# StearnsN2b.net
KiCad netlist of a schematic drawn in EAGLE
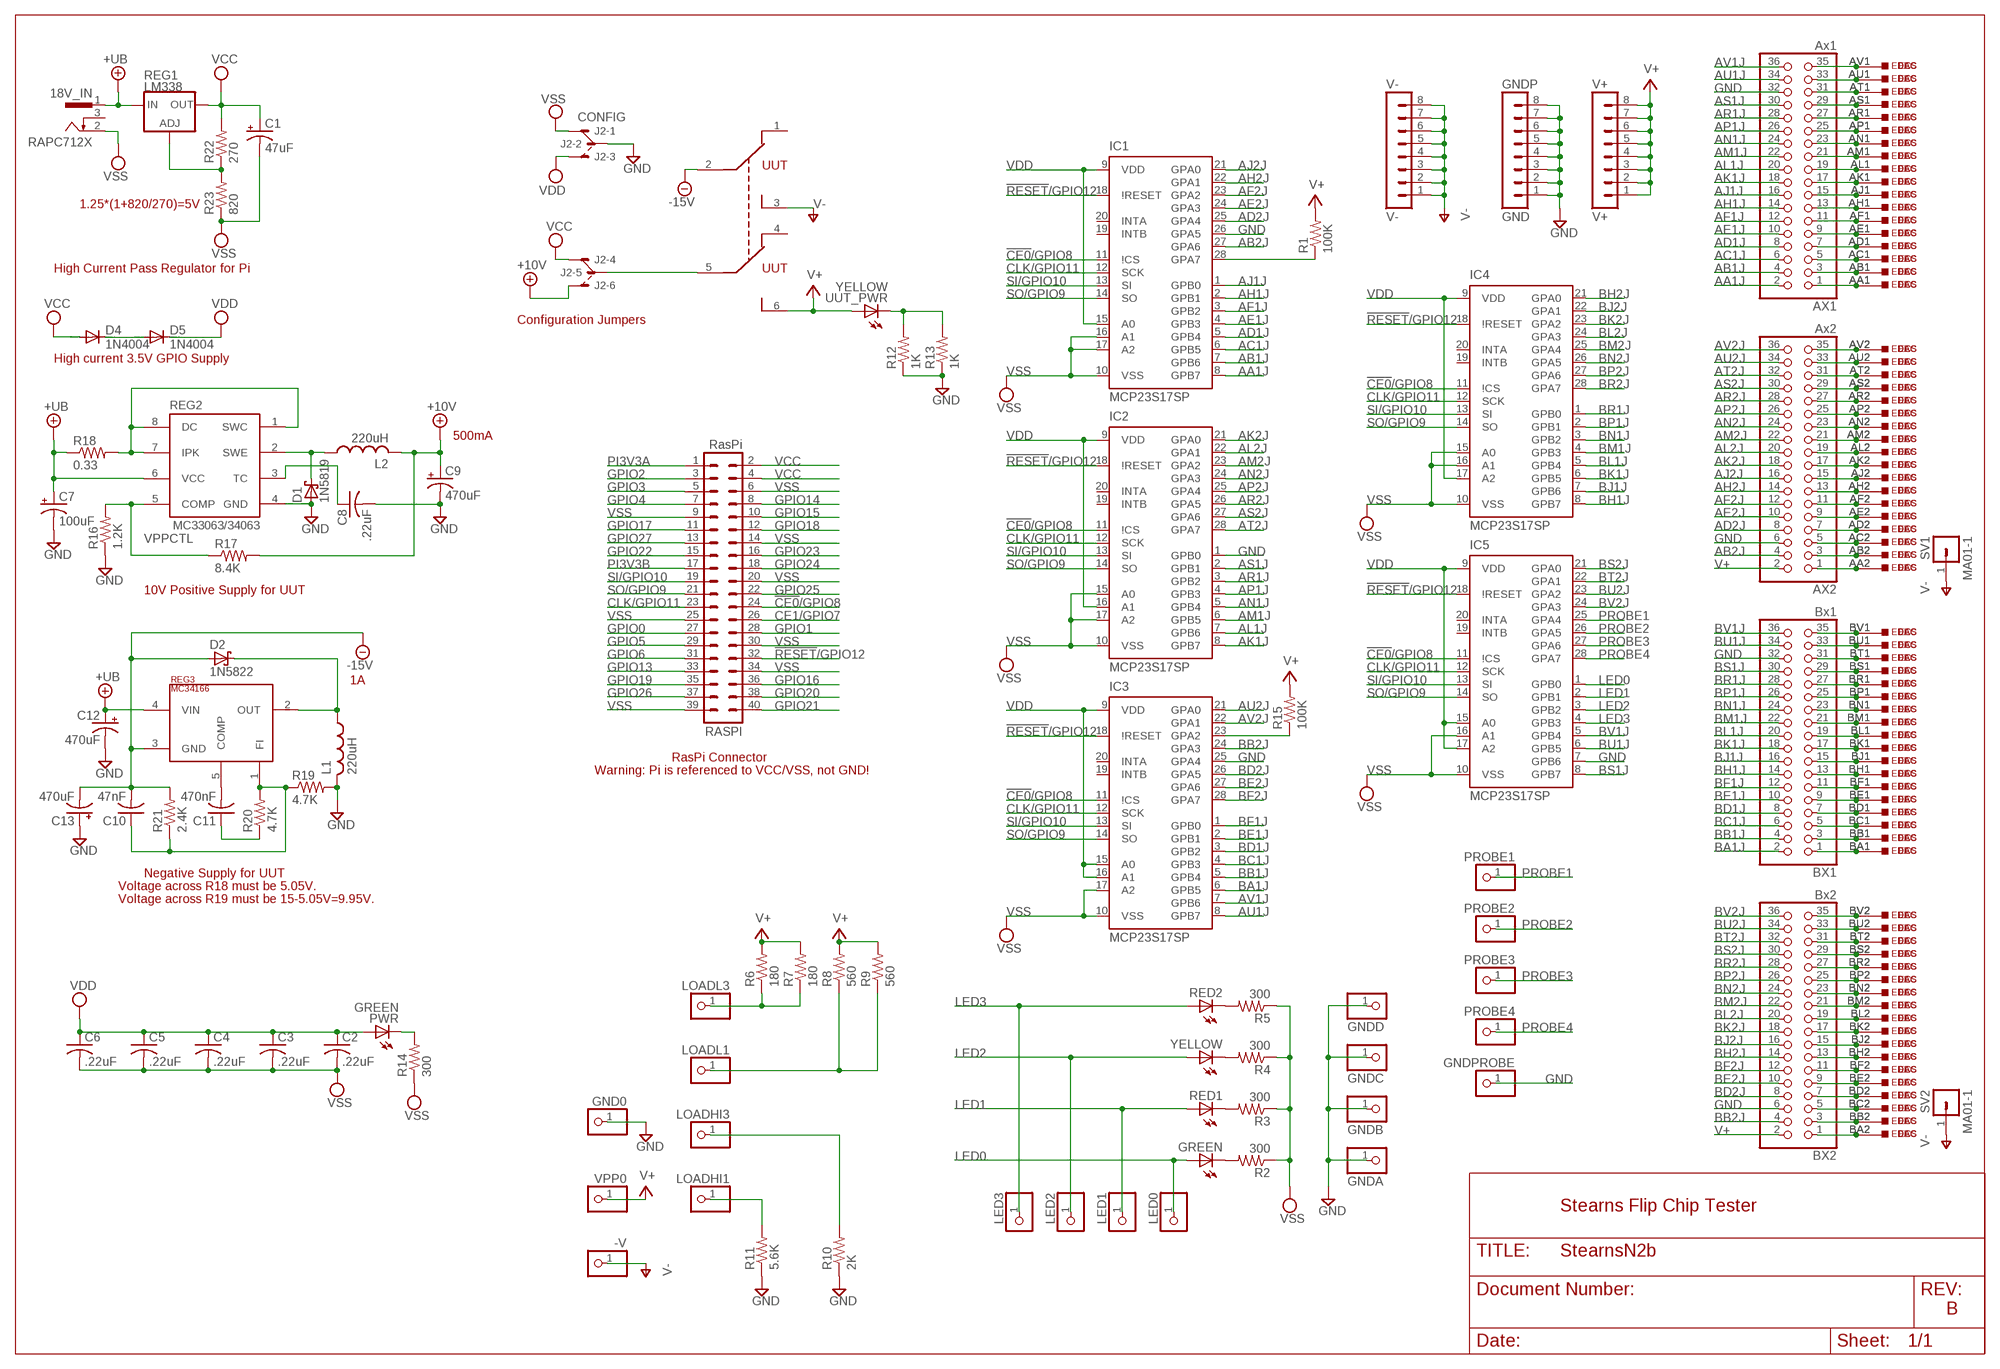
[diagram p0: schematic, sheet 1]

(export (version "E")
  (design (tool "Eeschema 10.0.6"))
  (components
    (comp (ref "-V")
      (value "PINHD-1X1")
      (footprint "eagle-import:1X01")
      (libsource (lib "eagle-import") (part "PINHD-1X1"))
    )
    (comp (ref "18V_IN")
      (value "RAPC712X")
      (footprint "eagle-import:SCD-014-A")
      (libsource (lib "eagle-import") (part "SCD-014A"))
    )
    (comp (ref "AX1")
      (value "Ax1")
      (footprint "eagle-import:2X18")
      (libsource (lib "eagle-import") (part "PINHD-2X18"))
    )
    (comp (ref "AX2")
      (value "Ax2")
      (footprint "eagle-import:2X18")
      (libsource (lib "eagle-import") (part "PINHD-2X18"))
    )
    (comp (ref "BX1")
      (value "Bx1")
      (footprint "eagle-import:2X18")
      (libsource (lib "eagle-import") (part "PINHD-2X18"))
    )
    (comp (ref "BX2")
      (value "Bx2")
      (footprint "eagle-import:2X18")
      (libsource (lib "eagle-import") (part "PINHD-2X18"))
    )
    (comp (ref "C1")
      (value "47uF")
      (footprint "eagle-import:E5-8,5")
      (libsource (lib "eagle-import") (part "CPOL-USE5-8.5"))
    )
    (comp (ref "C2")
      (value ".22uF")
      (footprint "eagle-import:C050-025X075")
      (libsource (lib "eagle-import") (part "C-US050-025X075"))
    )
    (comp (ref "C3")
      (value ".22uF")
      (footprint "eagle-import:C050-025X075")
      (libsource (lib "eagle-import") (part "C-US050-025X075"))
    )
    (comp (ref "C4")
      (value ".22uF")
      (footprint "eagle-import:C050-025X075")
      (libsource (lib "eagle-import") (part "C-US050-025X075"))
    )
    (comp (ref "C5")
      (value ".22uF")
      (footprint "eagle-import:C050-025X075")
      (libsource (lib "eagle-import") (part "C-US050-025X075"))
    )
    (comp (ref "C6")
      (value ".22uF")
      (footprint "eagle-import:C050-025X075")
      (libsource (lib "eagle-import") (part "C-US050-025X075"))
    )
    (comp (ref "C7")
      (value "100uF")
      (footprint "eagle-import:TT2D7")
      (libsource (lib "eagle-import") (part "CPOL-USTT2D7"))
    )
    (comp (ref "C8")
      (value ".22uF")
      (footprint "eagle-import:C050-025X075")
      (libsource (lib "eagle-import") (part "C-US050-025X075"))
    )
    (comp (ref "C9")
      (value "470uF")
      (footprint "eagle-import:E5-8,5")
      (libsource (lib "eagle-import") (part "CPOL-USE5-8.5"))
    )
    (comp (ref "C10")
      (value "47nF")
      (footprint "eagle-import:C050-025X075")
      (libsource (lib "eagle-import") (part "C-US050-025X075"))
    )
    (comp (ref "C11")
      (value "470nF")
      (footprint "eagle-import:C050-025X075")
      (libsource (lib "eagle-import") (part "C-US050-025X075"))
    )
    (comp (ref "C12")
      (value "470uF")
      (footprint "eagle-import:E5-8,5")
      (libsource (lib "eagle-import") (part "CPOL-USE5-8.5"))
    )
    (comp (ref "C13")
      (value "470uF")
      (footprint "eagle-import:E5-8,5")
      (libsource (lib "eagle-import") (part "CPOL-USE5-8.5"))
    )
    (comp (ref "D1")
      (value "1N5819")
      (footprint "eagle-import:DO35-7")
      (libsource (lib "eagle-import") (part "SCHOTTKY-DIODEDO35-7"))
    )
    (comp (ref "D2")
      (value "1N5822")
      (footprint "eagle-import:DO201T15")
      (libsource (lib "eagle-import") (part "SCHOTTKY-DIODEDO201T15"))
    )
    (comp (ref "D4")
      (value "1N4004")
      (footprint "eagle-import:DO41-10")
      (libsource (lib "eagle-import") (part "1N4004"))
    )
    (comp (ref "D5")
      (value "1N4004")
      (footprint "eagle-import:DO41-10")
      (libsource (lib "eagle-import") (part "1N4004"))
    )
    (comp (ref "DEC")
      (value "W971")
      (footprint "eagle-import:H807-2")
      (libsource (lib "eagle-import") (part "W971"))
    )
    (comp (ref "ECS")
      (value "W971ECS")
      (footprint "eagle-import:ECS2418-2")
      (libsource (lib "eagle-import") (part "W971ECS"))
    )
    (comp (ref "EDAC")
      (value "W971EDAC")
      (footprint "eagle-import:EDAC346-36-2")
      (libsource (lib "eagle-import") (part "W971EDAC"))
    )
    (comp (ref "GND0")
      (value "PINHD-1X1")
      (footprint "eagle-import:1X01")
      (libsource (lib "eagle-import") (part "PINHD-1X1"))
    )
    (comp (ref "GNDA")
      (value "PINHD-1X1")
      (footprint "eagle-import:1X01")
      (libsource (lib "eagle-import") (part "PINHD-1X1"))
    )
    (comp (ref "GNDB")
      (value "PINHD-1X1")
      (footprint "eagle-import:1X01")
      (libsource (lib "eagle-import") (part "PINHD-1X1"))
    )
    (comp (ref "GNDC")
      (value "PINHD-1X1")
      (footprint "eagle-import:1X01")
      (libsource (lib "eagle-import") (part "PINHD-1X1"))
    )
    (comp (ref "GNDD")
      (value "PINHD-1X1")
      (footprint "eagle-import:1X01")
      (libsource (lib "eagle-import") (part "PINHD-1X1"))
    )
    (comp (ref "GNDP")
      (value "GND")
      (footprint "eagle-import:MA08-1")
      (libsource (lib "eagle-import") (part "MA08-1"))
    )
    (comp (ref "GNDPROBE")
      (value "PINHD-1X1")
      (footprint "eagle-import:1X01")
      (libsource (lib "eagle-import") (part "PINHD-1X1"))
    )
    (comp (ref "GREEN")
      (value "LED5MM")
      (footprint "eagle-import:LED5MM")
      (libsource (lib "eagle-import") (part "LED5MM"))
    )
    (comp (ref "IC1")
      (value "MCP23S17SP")
      (footprint "eagle-import:DIL28-3")
      (libsource (lib "eagle-import") (part "MCP23S17SP"))
    )
    (comp (ref "IC2")
      (value "MCP23S17SP")
      (footprint "eagle-import:DIL28-3")
      (libsource (lib "eagle-import") (part "MCP23S17SP"))
    )
    (comp (ref "IC3")
      (value "MCP23S17SP")
      (footprint "eagle-import:DIL28-3")
      (libsource (lib "eagle-import") (part "MCP23S17SP"))
    )
    (comp (ref "IC4")
      (value "MCP23S17SP")
      (footprint "eagle-import:DIL28-3")
      (libsource (lib "eagle-import") (part "MCP23S17SP"))
    )
    (comp (ref "IC5")
      (value "MCP23S17SP")
      (footprint "eagle-import:DIL28-3")
      (libsource (lib "eagle-import") (part "MCP23S17SP"))
    )
    (comp (ref "J2")
      (value "CONFIG")
      (footprint "eagle-import:22-23-2061")
      (fields (field (name "MF") "MOLEX") (field (name "MPN") "22-23-2061"))
      (libsource (lib "eagle-import") (part "22-23-2061"))
    )
    (comp (ref "L1")
      (value "220uH")
      (footprint "eagle-import:6000-XXXX-RC")
      (libsource (lib "eagle-import") (part "L-US6000-XXX-RC"))
    )
    (comp (ref "L2")
      (value "220uH")
      (footprint "eagle-import:6000-XXXX-RC")
      (libsource (lib "eagle-import") (part "L-US6000-XXX-RC"))
    )
    (comp (ref "LED0")
      (value "PINHD-1X1")
      (footprint "eagle-import:1X01")
      (libsource (lib "eagle-import") (part "PINHD-1X1"))
    )
    (comp (ref "LED1")
      (value "PINHD-1X1")
      (footprint "eagle-import:1X01")
      (libsource (lib "eagle-import") (part "PINHD-1X1"))
    )
    (comp (ref "LED2")
      (value "PINHD-1X1")
      (footprint "eagle-import:1X01")
      (libsource (lib "eagle-import") (part "PINHD-1X1"))
    )
    (comp (ref "LED3")
      (value "PINHD-1X1")
      (footprint "eagle-import:1X01")
      (libsource (lib "eagle-import") (part "PINHD-1X1"))
    )
    (comp (ref "LOADHI1")
      (value "PINHD-1X1")
      (footprint "eagle-import:1X01")
      (libsource (lib "eagle-import") (part "PINHD-1X1"))
    )
    (comp (ref "LOADHI3")
      (value "PINHD-1X1")
      (footprint "eagle-import:1X01")
      (libsource (lib "eagle-import") (part "PINHD-1X1"))
    )
    (comp (ref "LOADL1")
      (value "PINHD-1X1")
      (footprint "eagle-import:1X01")
      (libsource (lib "eagle-import") (part "PINHD-1X1"))
    )
    (comp (ref "LOADL3")
      (value "PINHD-1X1")
      (footprint "eagle-import:1X01")
      (libsource (lib "eagle-import") (part "PINHD-1X1"))
    )
    (comp (ref "PROBE1")
      (value "PINHD-1X1")
      (footprint "eagle-import:1X01")
      (libsource (lib "eagle-import") (part "PINHD-1X1"))
    )
    (comp (ref "PROBE2")
      (value "PINHD-1X1")
      (footprint "eagle-import:1X01")
      (libsource (lib "eagle-import") (part "PINHD-1X1"))
    )
    (comp (ref "PROBE3")
      (value "PINHD-1X1")
      (footprint "eagle-import:1X01")
      (libsource (lib "eagle-import") (part "PINHD-1X1"))
    )
    (comp (ref "PROBE4")
      (value "PINHD-1X1")
      (footprint "eagle-import:1X01")
      (libsource (lib "eagle-import") (part "PINHD-1X1"))
    )
    (comp (ref "PWR")
      (value "GREEN")
      (footprint "eagle-import:LED5MM")
      (libsource (lib "eagle-import") (part "LED5MM"))
    )
    (comp (ref "R1")
      (value "100K")
      (footprint "eagle-import:0207_10")
      (libsource (lib "eagle-import") (part "R-US_0207/10"))
    )
    (comp (ref "R2")
      (value "300")
      (footprint "eagle-import:0207_10")
      (libsource (lib "eagle-import") (part "R-US_0207/10"))
    )
    (comp (ref "R3")
      (value "300")
      (footprint "eagle-import:0207_10")
      (libsource (lib "eagle-import") (part "R-US_0207/10"))
    )
    (comp (ref "R4")
      (value "300")
      (footprint "eagle-import:0207_10")
      (libsource (lib "eagle-import") (part "R-US_0207/10"))
    )
    (comp (ref "R5")
      (value "300")
      (footprint "eagle-import:0207_10")
      (libsource (lib "eagle-import") (part "R-US_0207/10"))
    )
    (comp (ref "R6")
      (value "180")
      (footprint "eagle-import:0207_10")
      (libsource (lib "eagle-import") (part "R-US_0207/10"))
    )
    (comp (ref "R7")
      (value "180")
      (footprint "eagle-import:0207_10")
      (libsource (lib "eagle-import") (part "R-US_0207/10"))
    )
    (comp (ref "R8")
      (value "560")
      (footprint "eagle-import:0207_10")
      (libsource (lib "eagle-import") (part "R-US_0207/10"))
    )
    (comp (ref "R9")
      (value "560")
      (footprint "eagle-import:0207_10")
      (libsource (lib "eagle-import") (part "R-US_0207/10"))
    )
    (comp (ref "R10")
      (value "2K")
      (footprint "eagle-import:0207_10")
      (libsource (lib "eagle-import") (part "R-US_0207/10"))
    )
    (comp (ref "R11")
      (value "5.6K")
      (footprint "eagle-import:0207_10")
      (libsource (lib "eagle-import") (part "R-US_0207/10"))
    )
    (comp (ref "R12")
      (value "1K")
      (footprint "eagle-import:0207_10")
      (libsource (lib "eagle-import") (part "R-US_0207/10"))
    )
    (comp (ref "R13")
      (value "1K")
      (footprint "eagle-import:0207_10")
      (libsource (lib "eagle-import") (part "R-US_0207/10"))
    )
    (comp (ref "R14")
      (value "300")
      (footprint "eagle-import:0207_10")
      (libsource (lib "eagle-import") (part "R-US_0207/10"))
    )
    (comp (ref "R15")
      (value "100K")
      (footprint "eagle-import:0207_10")
      (libsource (lib "eagle-import") (part "R-US_0207/10"))
    )
    (comp (ref "R16")
      (value "1.2K")
      (footprint "eagle-import:0207_10")
      (libsource (lib "eagle-import") (part "R-US_0207/10"))
    )
    (comp (ref "R17")
      (value "8.4K")
      (footprint "eagle-import:0207_10")
      (libsource (lib "eagle-import") (part "R-US_0207/10"))
    )
    (comp (ref "R18")
      (value "0.33")
      (footprint "eagle-import:0207_10")
      (libsource (lib "eagle-import") (part "R-US_0207/10"))
    )
    (comp (ref "R19")
      (value "4.7K")
      (footprint "eagle-import:0207_10")
      (libsource (lib "eagle-import") (part "R-US_0207/10"))
    )
    (comp (ref "R20")
      (value "4.7K")
      (footprint "eagle-import:0207_10")
      (libsource (lib "eagle-import") (part "R-US_0207/10"))
    )
    (comp (ref "R21")
      (value "2.4K")
      (footprint "eagle-import:0207_10")
      (libsource (lib "eagle-import") (part "R-US_0207/10"))
    )
    (comp (ref "R22")
      (value "270")
      (footprint "eagle-import:0207_10")
      (libsource (lib "eagle-import") (part "R-US_0207/10"))
    )
    (comp (ref "R23")
      (value "820")
      (footprint "eagle-import:0207_10")
      (libsource (lib "eagle-import") (part "R-US_0207/10"))
    )
    (comp (ref "RASPI")
      (value "RasPi")
      (footprint "eagle-import:MA20-2")
      (libsource (lib "eagle-import") (part "MA20-2"))
    )
    (comp (ref "RED1")
      (value "LED5MM")
      (footprint "eagle-import:LED5MM")
      (libsource (lib "eagle-import") (part "LED5MM"))
    )
    (comp (ref "RED2")
      (value "LED5MM")
      (footprint "eagle-import:LED5MM")
      (libsource (lib "eagle-import") (part "LED5MM"))
    )
    (comp (ref "REG1")
      (value "LM338")
      (footprint "eagle-import:TO220L1")
      (libsource (lib "eagle-import") (part "LM138-TL"))
    )
    (comp (ref "REG2")
      (value "MC33063/MC34063P")
      (footprint "eagle-import:DIL08")
      (libsource (lib "eagle-import") (part "MC33063/MC34063P"))
    )
    (comp (ref "REG3")
      (value "MC34166")
      (footprint "eagle-import:TO220-52")
      (libsource (lib "eagle-import") (part "MC34166"))
    )
    (comp (ref "SV1")
      (value "MA01-1")
      (footprint "eagle-import:MA01-1")
      (libsource (lib "eagle-import") (part "MA01-1"))
    )
    (comp (ref "SV2")
      (value "MA01-1")
      (footprint "eagle-import:MA01-1")
      (libsource (lib "eagle-import") (part "MA01-1"))
    )
    (comp (ref "UUT")
      (value "720X")
      (footprint "eagle-import:7209MD9V3")
      (libsource (lib "eagle-import") (part "720X"))
    )
    (comp (ref "UUT_PWR")
      (value "YELLOW")
      (footprint "eagle-import:LED5MM")
      (libsource (lib "eagle-import") (part "LED5MM"))
    )
    (comp (ref "V+")
      (value "V+")
      (footprint "eagle-import:MA08-1")
      (libsource (lib "eagle-import") (part "MA08-1"))
    )
    (comp (ref "V-")
      (value "V-")
      (footprint "eagle-import:MA08-1")
      (libsource (lib "eagle-import") (part "MA08-1"))
    )
    (comp (ref "VPP0")
      (value "PINHD-1X1")
      (footprint "eagle-import:1X01")
      (libsource (lib "eagle-import") (part "PINHD-1X1"))
    )
    (comp (ref "YELLOW")
      (value "LED5MM")
      (footprint "eagle-import:LED5MM")
      (libsource (lib "eagle-import") (part "LED5MM"))
    )
  )
  (nets
    (net (code "1") (name "+10V") (class "Default")
      (node (ref "C9") (pin "+") (pinfunction "+_+") (pintype "passive"))
      (node (ref "J2") (pin "6") (pinfunction "S_6") (pintype "passive"))
      (node (ref "L2") (pin "2") (pinfunction "2_2") (pintype "passive"))
      (node (ref "R17") (pin "2") (pinfunction "2_2") (pintype "passive"))
    )
    (net (code "2") (name "+UB") (class "Default")
      (node (ref "18V_IN") (pin "1") (pinfunction "1_1") (pintype "passive"))
      (node (ref "C12") (pin "+") (pinfunction "+_+") (pintype "passive"))
      (node (ref "C7") (pin "+") (pinfunction "+_+") (pintype "passive"))
      (node (ref "R18") (pin "1") (pinfunction "1_1") (pintype "passive"))
      (node (ref "REG1") (pin "3") (pinfunction "IN_3") (pintype "input"))
      (node (ref "REG2") (pin "6") (pinfunction "VCC_6") (pintype "power_in"))
      (node (ref "REG3") (pin "4") (pinfunction "VIN_4") (pintype "input"))
    )
    (net (code "3") (name "-15V") (class "Default")
      (node (ref "C10") (pin "2") (pinfunction "2_2") (pintype "passive"))
      (node (ref "C13") (pin "-") (pinfunction "-_-") (pintype "passive"))
      (node (ref "D2") (pin "A") (pinfunction "A_A") (pintype "passive"))
      (node (ref "R21") (pin "2") (pinfunction "2_2") (pintype "passive"))
      (node (ref "REG3") (pin "3") (pinfunction "GND_3") (pintype "input"))
      (node (ref "UUT") (pin "2") (pinfunction "A2_2") (pintype "bidirectional"))
    )
    (net (code "4") (name "/AA1J") (class "Default")
      (node (ref "AX1") (pin "2") (pinfunction "2_2") (pintype "passive"))
      (node (ref "IC1") (pin "8") (pinfunction "GPB7_8") (pintype "bidirectional"))
    )
    (net (code "5") (name "/AB1J") (class "Default")
      (node (ref "AX1") (pin "4") (pinfunction "4_4") (pintype "passive"))
      (node (ref "IC1") (pin "7") (pinfunction "GPB6_7") (pintype "bidirectional"))
    )
    (net (code "6") (name "/AB2J") (class "Default")
      (node (ref "AX2") (pin "4") (pinfunction "4_4") (pintype "passive"))
      (node (ref "IC1") (pin "27") (pinfunction "GPA6_27") (pintype "bidirectional"))
    )
    (net (code "7") (name "/AC1J") (class "Default")
      (node (ref "AX1") (pin "6") (pinfunction "6_6") (pintype "passive"))
      (node (ref "IC1") (pin "6") (pinfunction "GPB5_6") (pintype "bidirectional"))
    )
    (net (code "8") (name "/AD1J") (class "Default")
      (node (ref "AX1") (pin "8") (pinfunction "8_8") (pintype "passive"))
      (node (ref "IC1") (pin "5") (pinfunction "GPB4_5") (pintype "bidirectional"))
    )
    (net (code "9") (name "/AD2J") (class "Default")
      (node (ref "AX2") (pin "8") (pinfunction "8_8") (pintype "passive"))
      (node (ref "IC1") (pin "25") (pinfunction "GPA4_25") (pintype "bidirectional"))
    )
    (net (code "10") (name "/AE1J") (class "Default")
      (node (ref "AX1") (pin "10") (pinfunction "10_10") (pintype "passive"))
      (node (ref "IC1") (pin "4") (pinfunction "GPB3_4") (pintype "bidirectional"))
    )
    (net (code "11") (name "/AE2J") (class "Default")
      (node (ref "AX2") (pin "10") (pinfunction "10_10") (pintype "passive"))
      (node (ref "IC1") (pin "24") (pinfunction "GPA3_24") (pintype "bidirectional"))
    )
    (net (code "12") (name "/AF1J") (class "Default")
      (node (ref "AX1") (pin "12") (pinfunction "12_12") (pintype "passive"))
      (node (ref "IC1") (pin "3") (pinfunction "GPB2_3") (pintype "bidirectional"))
    )
    (net (code "13") (name "/AF2J") (class "Default")
      (node (ref "AX2") (pin "12") (pinfunction "12_12") (pintype "passive"))
      (node (ref "IC1") (pin "23") (pinfunction "GPA2_23") (pintype "bidirectional"))
    )
    (net (code "14") (name "/AH1J") (class "Default")
      (node (ref "AX1") (pin "14") (pinfunction "14_14") (pintype "passive"))
      (node (ref "IC1") (pin "2") (pinfunction "GPB1_2") (pintype "bidirectional"))
    )
    (net (code "15") (name "/AH2J") (class "Default")
      (node (ref "AX2") (pin "14") (pinfunction "14_14") (pintype "passive"))
      (node (ref "IC1") (pin "22") (pinfunction "GPA1_22") (pintype "bidirectional"))
    )
    (net (code "16") (name "/AJ1J") (class "Default")
      (node (ref "AX1") (pin "16") (pinfunction "16_16") (pintype "passive"))
      (node (ref "IC1") (pin "1") (pinfunction "GPB0_1") (pintype "bidirectional"))
    )
    (net (code "17") (name "/AJ2J") (class "Default")
      (node (ref "AX2") (pin "16") (pinfunction "16_16") (pintype "passive"))
      (node (ref "IC1") (pin "21") (pinfunction "GPA0_21") (pintype "bidirectional"))
    )
    (net (code "18") (name "/AK1J") (class "Default")
      (node (ref "AX1") (pin "18") (pinfunction "18_18") (pintype "passive"))
      (node (ref "IC2") (pin "8") (pinfunction "GPB7_8") (pintype "bidirectional"))
    )
    (net (code "19") (name "/AK2J") (class "Default")
      (node (ref "AX2") (pin "18") (pinfunction "18_18") (pintype "passive"))
      (node (ref "IC2") (pin "21") (pinfunction "GPA0_21") (pintype "bidirectional"))
    )
    (net (code "20") (name "/AL1J") (class "Default")
      (node (ref "AX1") (pin "20") (pinfunction "20_20") (pintype "passive"))
      (node (ref "IC2") (pin "7") (pinfunction "GPB6_7") (pintype "bidirectional"))
    )
    (net (code "21") (name "/AL2J") (class "Default")
      (node (ref "AX2") (pin "20") (pinfunction "20_20") (pintype "passive"))
      (node (ref "IC2") (pin "22") (pinfunction "GPA1_22") (pintype "bidirectional"))
    )
    (net (code "22") (name "/AM1J") (class "Default")
      (node (ref "AX1") (pin "22") (pinfunction "22_22") (pintype "passive"))
      (node (ref "IC2") (pin "6") (pinfunction "GPB5_6") (pintype "bidirectional"))
    )
    (net (code "23") (name "/AM2J") (class "Default")
      (node (ref "AX2") (pin "22") (pinfunction "22_22") (pintype "passive"))
      (node (ref "IC2") (pin "23") (pinfunction "GPA2_23") (pintype "bidirectional"))
    )
    (net (code "24") (name "/AN1J") (class "Default")
      (node (ref "AX1") (pin "24") (pinfunction "24_24") (pintype "passive"))
      (node (ref "IC2") (pin "5") (pinfunction "GPB4_5") (pintype "bidirectional"))
    )
    (net (code "25") (name "/AN2J") (class "Default")
      (node (ref "AX2") (pin "24") (pinfunction "24_24") (pintype "passive"))
      (node (ref "IC2") (pin "24") (pinfunction "GPA3_24") (pintype "bidirectional"))
    )
    (net (code "26") (name "/AP1J") (class "Default")
      (node (ref "AX1") (pin "26") (pinfunction "26_26") (pintype "passive"))
      (node (ref "IC2") (pin "4") (pinfunction "GPB3_4") (pintype "bidirectional"))
    )
    (net (code "27") (name "/AP2J") (class "Default")
      (node (ref "AX2") (pin "26") (pinfunction "26_26") (pintype "passive"))
      (node (ref "IC2") (pin "25") (pinfunction "GPA4_25") (pintype "bidirectional"))
    )
    (net (code "28") (name "/AR1J") (class "Default")
      (node (ref "AX1") (pin "28") (pinfunction "28_28") (pintype "passive"))
      (node (ref "IC2") (pin "3") (pinfunction "GPB2_3") (pintype "bidirectional"))
    )
    (net (code "29") (name "/AR2J") (class "Default")
      (node (ref "AX2") (pin "28") (pinfunction "28_28") (pintype "passive"))
      (node (ref "IC2") (pin "26") (pinfunction "GPA5_26") (pintype "bidirectional"))
    )
    (net (code "30") (name "/AS1J") (class "Default")
      (node (ref "AX1") (pin "30") (pinfunction "30_30") (pintype "passive"))
      (node (ref "IC2") (pin "2") (pinfunction "GPB1_2") (pintype "bidirectional"))
    )
    (net (code "31") (name "/AS2J") (class "Default")
      (node (ref "AX2") (pin "30") (pinfunction "30_30") (pintype "passive"))
      (node (ref "IC2") (pin "27") (pinfunction "GPA6_27") (pintype "bidirectional"))
    )
    (net (code "32") (name "/AT2J") (class "Default")
      (node (ref "AX2") (pin "32") (pinfunction "32_32") (pintype "passive"))
      (node (ref "IC2") (pin "28") (pinfunction "GPA7_28") (pintype "bidirectional"))
    )
    (net (code "33") (name "/AU1J") (class "Default")
      (node (ref "AX1") (pin "34") (pinfunction "34_34") (pintype "passive"))
      (node (ref "IC3") (pin "8") (pinfunction "GPB7_8") (pintype "bidirectional"))
    )
    (net (code "34") (name "/AU2J") (class "Default")
      (node (ref "AX2") (pin "34") (pinfunction "34_34") (pintype "passive"))
      (node (ref "IC3") (pin "21") (pinfunction "GPA0_21") (pintype "bidirectional"))
    )
    (net (code "35") (name "/AV1J") (class "Default")
      (node (ref "AX1") (pin "36") (pinfunction "36_36") (pintype "passive"))
      (node (ref "IC3") (pin "7") (pinfunction "GPB6_7") (pintype "bidirectional"))
    )
    (net (code "36") (name "/AV2J") (class "Default")
      (node (ref "AX2") (pin "36") (pinfunction "36_36") (pintype "passive"))
      (node (ref "IC3") (pin "22") (pinfunction "GPA1_22") (pintype "bidirectional"))
    )
    (net (code "37") (name "/BA1J") (class "Default")
      (node (ref "BX1") (pin "2") (pinfunction "2_2") (pintype "passive"))
      (node (ref "IC3") (pin "6") (pinfunction "GPB5_6") (pintype "bidirectional"))
    )
    (net (code "38") (name "/BB1J") (class "Default")
      (node (ref "BX1") (pin "4") (pinfunction "4_4") (pintype "passive"))
      (node (ref "IC3") (pin "5") (pinfunction "GPB4_5") (pintype "bidirectional"))
    )
    (net (code "39") (name "/BB2J") (class "Default")
      (node (ref "BX2") (pin "4") (pinfunction "4_4") (pintype "passive"))
      (node (ref "IC3") (pin "24") (pinfunction "GPA3_24") (pintype "bidirectional"))
    )
    (net (code "40") (name "/BC1J") (class "Default")
      (node (ref "BX1") (pin "6") (pinfunction "6_6") (pintype "passive"))
      (node (ref "IC3") (pin "4") (pinfunction "GPB3_4") (pintype "bidirectional"))
    )
    (net (code "41") (name "/BD1J") (class "Default")
      (node (ref "BX1") (pin "8") (pinfunction "8_8") (pintype "passive"))
      (node (ref "IC3") (pin "3") (pinfunction "GPB2_3") (pintype "bidirectional"))
    )
    (net (code "42") (name "/BD2J") (class "Default")
      (node (ref "BX2") (pin "8") (pinfunction "8_8") (pintype "passive"))
      (node (ref "IC3") (pin "26") (pinfunction "GPA5_26") (pintype "bidirectional"))
    )
    (net (code "43") (name "/BE1J") (class "Default")
      (node (ref "BX1") (pin "10") (pinfunction "10_10") (pintype "passive"))
      (node (ref "IC3") (pin "2") (pinfunction "GPB1_2") (pintype "bidirectional"))
    )
    (net (code "44") (name "/BE2J") (class "Default")
      (node (ref "BX2") (pin "10") (pinfunction "10_10") (pintype "passive"))
      (node (ref "IC3") (pin "27") (pinfunction "GPA6_27") (pintype "bidirectional"))
    )
    (net (code "45") (name "/BF1J") (class "Default")
      (node (ref "BX1") (pin "12") (pinfunction "12_12") (pintype "passive"))
      (node (ref "IC3") (pin "1") (pinfunction "GPB0_1") (pintype "bidirectional"))
    )
    (net (code "46") (name "/BF2J") (class "Default")
      (node (ref "BX2") (pin "12") (pinfunction "12_12") (pintype "passive"))
      (node (ref "IC3") (pin "28") (pinfunction "GPA7_28") (pintype "bidirectional"))
    )
    (net (code "47") (name "/BH1J") (class "Default")
      (node (ref "BX1") (pin "14") (pinfunction "14_14") (pintype "passive"))
      (node (ref "IC4") (pin "8") (pinfunction "GPB7_8") (pintype "bidirectional"))
    )
    (net (code "48") (name "/BH2J") (class "Default")
      (node (ref "BX2") (pin "14") (pinfunction "14_14") (pintype "passive"))
      (node (ref "IC4") (pin "21") (pinfunction "GPA0_21") (pintype "bidirectional"))
    )
    (net (code "49") (name "/BJ1J") (class "Default")
      (node (ref "BX1") (pin "16") (pinfunction "16_16") (pintype "passive"))
      (node (ref "IC4") (pin "7") (pinfunction "GPB6_7") (pintype "bidirectional"))
    )
    (net (code "50") (name "/BJ2J") (class "Default")
      (node (ref "BX2") (pin "16") (pinfunction "16_16") (pintype "passive"))
      (node (ref "IC4") (pin "22") (pinfunction "GPA1_22") (pintype "bidirectional"))
    )
    (net (code "51") (name "/BK1J") (class "Default")
      (node (ref "BX1") (pin "18") (pinfunction "18_18") (pintype "passive"))
      (node (ref "IC4") (pin "6") (pinfunction "GPB5_6") (pintype "bidirectional"))
    )
    (net (code "52") (name "/BK2J") (class "Default")
      (node (ref "BX2") (pin "18") (pinfunction "18_18") (pintype "passive"))
      (node (ref "IC4") (pin "23") (pinfunction "GPA2_23") (pintype "bidirectional"))
    )
    (net (code "53") (name "/BL1J") (class "Default")
      (node (ref "BX1") (pin "20") (pinfunction "20_20") (pintype "passive"))
      (node (ref "IC4") (pin "5") (pinfunction "GPB4_5") (pintype "bidirectional"))
    )
    (net (code "54") (name "/BL2J") (class "Default")
      (node (ref "BX2") (pin "20") (pinfunction "20_20") (pintype "passive"))
      (node (ref "IC4") (pin "24") (pinfunction "GPA3_24") (pintype "bidirectional"))
    )
    (net (code "55") (name "/BM1J") (class "Default")
      (node (ref "BX1") (pin "22") (pinfunction "22_22") (pintype "passive"))
      (node (ref "IC4") (pin "4") (pinfunction "GPB3_4") (pintype "bidirectional"))
    )
    (net (code "56") (name "/BM2J") (class "Default")
      (node (ref "BX2") (pin "22") (pinfunction "22_22") (pintype "passive"))
      (node (ref "IC4") (pin "25") (pinfunction "GPA4_25") (pintype "bidirectional"))
    )
    (net (code "57") (name "/BN1J") (class "Default")
      (node (ref "BX1") (pin "24") (pinfunction "24_24") (pintype "passive"))
      (node (ref "IC4") (pin "3") (pinfunction "GPB2_3") (pintype "bidirectional"))
    )
    (net (code "58") (name "/BN2J") (class "Default")
      (node (ref "BX2") (pin "24") (pinfunction "24_24") (pintype "passive"))
      (node (ref "IC4") (pin "26") (pinfunction "GPA5_26") (pintype "bidirectional"))
    )
    (net (code "59") (name "/BP1J") (class "Default")
      (node (ref "BX1") (pin "26") (pinfunction "26_26") (pintype "passive"))
      (node (ref "IC4") (pin "2") (pinfunction "GPB1_2") (pintype "bidirectional"))
    )
    (net (code "60") (name "/BP2J") (class "Default")
      (node (ref "BX2") (pin "26") (pinfunction "26_26") (pintype "passive"))
      (node (ref "IC4") (pin "27") (pinfunction "GPA6_27") (pintype "bidirectional"))
    )
    (net (code "61") (name "/BR1J") (class "Default")
      (node (ref "BX1") (pin "28") (pinfunction "28_28") (pintype "passive"))
      (node (ref "IC4") (pin "1") (pinfunction "GPB0_1") (pintype "bidirectional"))
    )
    (net (code "62") (name "/BR2J") (class "Default")
      (node (ref "BX2") (pin "28") (pinfunction "28_28") (pintype "passive"))
      (node (ref "IC4") (pin "28") (pinfunction "GPA7_28") (pintype "bidirectional"))
    )
    (net (code "63") (name "/BS1J") (class "Default")
      (node (ref "BX1") (pin "30") (pinfunction "30_30") (pintype "passive"))
      (node (ref "IC5") (pin "8") (pinfunction "GPB7_8") (pintype "bidirectional"))
    )
    (net (code "64") (name "/BS2J") (class "Default")
      (node (ref "BX2") (pin "30") (pinfunction "30_30") (pintype "passive"))
      (node (ref "IC5") (pin "21") (pinfunction "GPA0_21") (pintype "bidirectional"))
    )
    (net (code "65") (name "/BT2J") (class "Default")
      (node (ref "BX2") (pin "32") (pinfunction "32_32") (pintype "passive"))
      (node (ref "IC5") (pin "22") (pinfunction "GPA1_22") (pintype "bidirectional"))
    )
    (net (code "66") (name "/BU1J") (class "Default")
      (node (ref "BX1") (pin "34") (pinfunction "34_34") (pintype "passive"))
      (node (ref "IC5") (pin "6") (pinfunction "GPB5_6") (pintype "bidirectional"))
    )
    (net (code "67") (name "/BU2J") (class "Default")
      (node (ref "BX2") (pin "34") (pinfunction "34_34") (pintype "passive"))
      (node (ref "IC5") (pin "23") (pinfunction "GPA2_23") (pintype "bidirectional"))
    )
    (net (code "68") (name "/BV1J") (class "Default")
      (node (ref "BX1") (pin "36") (pinfunction "36_36") (pintype "passive"))
      (node (ref "IC5") (pin "5") (pinfunction "GPB4_5") (pintype "bidirectional"))
    )
    (net (code "69") (name "/BV2J") (class "Default")
      (node (ref "BX2") (pin "36") (pinfunction "36_36") (pintype "passive"))
      (node (ref "IC5") (pin "24") (pinfunction "GPA3_24") (pintype "bidirectional"))
    )
    (net (code "70") (name "/CE1{slash}GPIO7") (class "Default")
      (node (ref "RASPI") (pin "26") (pinfunction "26_26") (pintype "passive"))
    )
    (net (code "71") (name "/CLK{slash}GPIO11") (class "Default")
      (node (ref "IC1") (pin "12") (pinfunction "SCK_12") (pintype "input"))
      (node (ref "IC2") (pin "12") (pinfunction "SCK_12") (pintype "input"))
      (node (ref "IC3") (pin "12") (pinfunction "SCK_12") (pintype "input"))
      (node (ref "IC4") (pin "12") (pinfunction "SCK_12") (pintype "input"))
      (node (ref "IC5") (pin "12") (pinfunction "SCK_12") (pintype "input"))
      (node (ref "RASPI") (pin "23") (pinfunction "23_23") (pintype "passive"))
    )
    (net (code "72") (name "/GPIO0") (class "Default")
      (node (ref "RASPI") (pin "27") (pinfunction "27_27") (pintype "passive"))
    )
    (net (code "73") (name "/GPIO1") (class "Default")
      (node (ref "RASPI") (pin "28") (pinfunction "28_28") (pintype "passive"))
    )
    (net (code "74") (name "/GPIO2") (class "Default")
      (node (ref "RASPI") (pin "3") (pinfunction "3_3") (pintype "passive"))
    )
    (net (code "75") (name "/GPIO3") (class "Default")
      (node (ref "RASPI") (pin "5") (pinfunction "5_5") (pintype "passive"))
    )
    (net (code "76") (name "/GPIO4") (class "Default")
      (node (ref "RASPI") (pin "7") (pinfunction "7_7") (pintype "passive"))
    )
    (net (code "77") (name "/GPIO5") (class "Default")
      (node (ref "RASPI") (pin "29") (pinfunction "29_29") (pintype "passive"))
    )
    (net (code "78") (name "/GPIO6") (class "Default")
      (node (ref "RASPI") (pin "31") (pinfunction "31_31") (pintype "passive"))
    )
    (net (code "79") (name "/GPIO13") (class "Default")
      (node (ref "RASPI") (pin "33") (pinfunction "33_33") (pintype "passive"))
    )
    (net (code "80") (name "/GPIO14") (class "Default")
      (node (ref "RASPI") (pin "8") (pinfunction "8_8") (pintype "passive"))
    )
    (net (code "81") (name "/GPIO15") (class "Default")
      (node (ref "RASPI") (pin "10") (pinfunction "10_10") (pintype "passive"))
    )
    (net (code "82") (name "/GPIO16") (class "Default")
      (node (ref "RASPI") (pin "36") (pinfunction "36_36") (pintype "passive"))
    )
    (net (code "83") (name "/GPIO17") (class "Default")
      (node (ref "RASPI") (pin "11") (pinfunction "11_11") (pintype "passive"))
    )
    (net (code "84") (name "/GPIO18") (class "Default")
      (node (ref "RASPI") (pin "12") (pinfunction "12_12") (pintype "passive"))
    )
    (net (code "85") (name "/GPIO19") (class "Default")
      (node (ref "RASPI") (pin "35") (pinfunction "35_35") (pintype "passive"))
    )
    (net (code "86") (name "/GPIO20") (class "Default")
      (node (ref "RASPI") (pin "38") (pinfunction "38_38") (pintype "passive"))
    )
    (net (code "87") (name "/GPIO21") (class "Default")
      (node (ref "RASPI") (pin "40") (pinfunction "40_40") (pintype "passive"))
    )
    (net (code "88") (name "/GPIO22") (class "Default")
      (node (ref "RASPI") (pin "15") (pinfunction "15_15") (pintype "passive"))
    )
    (net (code "89") (name "/GPIO23") (class "Default")
      (node (ref "RASPI") (pin "16") (pinfunction "16_16") (pintype "passive"))
    )
    (net (code "90") (name "/GPIO24") (class "Default")
      (node (ref "RASPI") (pin "18") (pinfunction "18_18") (pintype "passive"))
    )
    (net (code "91") (name "/GPIO25") (class "Default")
      (node (ref "RASPI") (pin "22") (pinfunction "22_22") (pintype "passive"))
    )
    (net (code "92") (name "/GPIO26") (class "Default")
      (node (ref "RASPI") (pin "37") (pinfunction "37_37") (pintype "passive"))
    )
    (net (code "93") (name "/GPIO27") (class "Default")
      (node (ref "RASPI") (pin "13") (pinfunction "13_13") (pintype "passive"))
    )
    (net (code "94") (name "/LED0") (class "Default")
      (node (ref "GREEN") (pin "A") (pinfunction "A_A") (pintype "passive"))
      (node (ref "IC5") (pin "1") (pinfunction "GPB0_1") (pintype "bidirectional"))
      (node (ref "LED0") (pin "1") (pinfunction "1_1") (pintype "passive"))
    )
    (net (code "95") (name "/LED1") (class "Default")
      (node (ref "IC5") (pin "2") (pinfunction "GPB1_2") (pintype "bidirectional"))
      (node (ref "LED1") (pin "1") (pinfunction "1_1") (pintype "passive"))
      (node (ref "RED1") (pin "A") (pinfunction "A_A") (pintype "passive"))
    )
    (net (code "96") (name "/LED2") (class "Default")
      (node (ref "IC5") (pin "3") (pinfunction "GPB2_3") (pintype "bidirectional"))
      (node (ref "LED2") (pin "1") (pinfunction "1_1") (pintype "passive"))
      (node (ref "YELLOW") (pin "A") (pinfunction "A_A") (pintype "passive"))
    )
    (net (code "97") (name "/LED3") (class "Default")
      (node (ref "IC5") (pin "4") (pinfunction "GPB3_4") (pintype "bidirectional"))
      (node (ref "LED3") (pin "1") (pinfunction "1_1") (pintype "passive"))
      (node (ref "RED2") (pin "A") (pinfunction "A_A") (pintype "passive"))
    )
    (net (code "98") (name "/PI3V3A") (class "Default")
      (node (ref "RASPI") (pin "1") (pinfunction "1_1") (pintype "passive"))
    )
    (net (code "99") (name "/PI3V3B") (class "Default")
      (node (ref "RASPI") (pin "17") (pinfunction "17_17") (pintype "passive"))
    )
    (net (code "100") (name "/PROBE1") (class "Default")
      (node (ref "IC5") (pin "25") (pinfunction "GPA4_25") (pintype "bidirectional"))
      (node (ref "PROBE1") (pin "1") (pinfunction "1_1") (pintype "passive"))
    )
    (net (code "101") (name "/PROBE2") (class "Default")
      (node (ref "IC5") (pin "26") (pinfunction "GPA5_26") (pintype "bidirectional"))
      (node (ref "PROBE2") (pin "1") (pinfunction "1_1") (pintype "passive"))
    )
    (net (code "102") (name "/PROBE3") (class "Default")
      (node (ref "IC5") (pin "27") (pinfunction "GPA6_27") (pintype "bidirectional"))
      (node (ref "PROBE3") (pin "1") (pinfunction "1_1") (pintype "passive"))
    )
    (net (code "103") (name "/PROBE4") (class "Default")
      (node (ref "IC5") (pin "28") (pinfunction "GPA7_28") (pintype "bidirectional"))
      (node (ref "PROBE4") (pin "1") (pinfunction "1_1") (pintype "passive"))
    )
    (net (code "104") (name "/SI{slash}GPIO10") (class "Default")
      (node (ref "IC1") (pin "13") (pinfunction "SI_13") (pintype "input"))
      (node (ref "IC2") (pin "13") (pinfunction "SI_13") (pintype "input"))
      (node (ref "IC3") (pin "13") (pinfunction "SI_13") (pintype "input"))
      (node (ref "IC4") (pin "13") (pinfunction "SI_13") (pintype "input"))
      (node (ref "IC5") (pin "13") (pinfunction "SI_13") (pintype "input"))
      (node (ref "RASPI") (pin "19") (pinfunction "19_19") (pintype "passive"))
    )
    (net (code "105") (name "/SO{slash}GPIO9") (class "Default")
      (node (ref "IC1") (pin "14") (pinfunction "SO_14") (pintype "output"))
      (node (ref "IC2") (pin "14") (pinfunction "SO_14") (pintype "output"))
      (node (ref "IC3") (pin "14") (pinfunction "SO_14") (pintype "output"))
      (node (ref "IC4") (pin "14") (pinfunction "SO_14") (pintype "output"))
      (node (ref "IC5") (pin "14") (pinfunction "SO_14") (pintype "output"))
      (node (ref "RASPI") (pin "21") (pinfunction "21_21") (pintype "passive"))
    )
    (net (code "106") (name "/VPPCTL") (class "Default")
      (node (ref "R16") (pin "2") (pinfunction "2_2") (pintype "passive"))
      (node (ref "R17") (pin "1") (pinfunction "1_1") (pintype "passive"))
      (node (ref "REG2") (pin "5") (pinfunction "COMP_5") (pintype "input"))
    )
    (net (code "107") (name "/~{CE0}{slash}GPIO8") (class "Default")
      (node (ref "IC1") (pin "11") (pinfunction "\\~{CS}_11") (pintype "input"))
      (node (ref "IC2") (pin "11") (pinfunction "\\~{CS}_11") (pintype "input"))
      (node (ref "IC3") (pin "11") (pinfunction "\\~{CS}_11") (pintype "input"))
      (node (ref "IC4") (pin "11") (pinfunction "\\~{CS}_11") (pintype "input"))
      (node (ref "IC5") (pin "11") (pinfunction "\\~{CS}_11") (pintype "input"))
      (node (ref "RASPI") (pin "24") (pinfunction "24_24") (pintype "passive"))
    )
    (net (code "108") (name "/~{RESET}{slash}GPIO12") (class "Default")
      (node (ref "IC1") (pin "18") (pinfunction "\\~{RESET}_18") (pintype "input"))
      (node (ref "IC2") (pin "18") (pinfunction "\\~{RESET}_18") (pintype "input"))
      (node (ref "IC3") (pin "18") (pinfunction "\\~{RESET}_18") (pintype "input"))
      (node (ref "IC4") (pin "18") (pinfunction "\\~{RESET}_18") (pintype "input"))
      (node (ref "IC5") (pin "18") (pinfunction "\\~{RESET}_18") (pintype "input"))
      (node (ref "RASPI") (pin "32") (pinfunction "32_32") (pintype "passive"))
    )
    (net (code "109") (name "GND") (class "Default")
      (node (ref "AX1") (pin "32") (pinfunction "32_32") (pintype "passive"))
      (node (ref "AX2") (pin "6") (pinfunction "6_6") (pintype "passive"))
      (node (ref "BX1") (pin "32") (pinfunction "32_32") (pintype "passive"))
      (node (ref "BX2") (pin "6") (pinfunction "6_6") (pintype "passive"))
      (node (ref "C12") (pin "-") (pinfunction "-_-") (pintype "passive"))
      (node (ref "C13") (pin "+") (pinfunction "+_+") (pintype "passive"))
      (node (ref "C7") (pin "-") (pinfunction "-_-") (pintype "passive"))
      (node (ref "C8") (pin "2") (pinfunction "2_2") (pintype "passive"))
      (node (ref "C9") (pin "-") (pinfunction "-_-") (pintype "passive"))
      (node (ref "D1") (pin "A") (pinfunction "A_A") (pintype "passive"))
      (node (ref "GND0") (pin "1") (pinfunction "1_1") (pintype "passive"))
      (node (ref "GNDA") (pin "1") (pinfunction "1_1") (pintype "passive"))
      (node (ref "GNDB") (pin "1") (pinfunction "1_1") (pintype "passive"))
      (node (ref "GNDC") (pin "1") (pinfunction "1_1") (pintype "passive"))
      (node (ref "GNDD") (pin "1") (pinfunction "1_1") (pintype "passive"))
      (node (ref "GNDP") (pin "1") (pinfunction "1_1") (pintype "passive"))
      (node (ref "GNDP") (pin "2") (pinfunction "2_2") (pintype "passive"))
      (node (ref "GNDP") (pin "3") (pinfunction "3_3") (pintype "passive"))
      (node (ref "GNDP") (pin "4") (pinfunction "4_4") (pintype "passive"))
      (node (ref "GNDP") (pin "5") (pinfunction "5_5") (pintype "passive"))
      (node (ref "GNDP") (pin "6") (pinfunction "6_6") (pintype "passive"))
      (node (ref "GNDP") (pin "7") (pinfunction "7_7") (pintype "passive"))
      (node (ref "GNDP") (pin "8") (pinfunction "8_8") (pintype "passive"))
      (node (ref "GNDPROBE") (pin "1") (pinfunction "1_1") (pintype "passive"))
      (node (ref "IC1") (pin "26") (pinfunction "GPA5_26") (pintype "bidirectional"))
      (node (ref "IC2") (pin "1") (pinfunction "GPB0_1") (pintype "bidirectional"))
      (node (ref "IC3") (pin "25") (pinfunction "GPA4_25") (pintype "bidirectional"))
      (node (ref "IC5") (pin "7") (pinfunction "GPB6_7") (pintype "bidirectional"))
      (node (ref "J2") (pin "2") (pinfunction "S_2") (pintype "passive"))
      (node (ref "L1") (pin "2") (pinfunction "2_2") (pintype "passive"))
      (node (ref "R10") (pin "1") (pinfunction "1_1") (pintype "passive"))
      (node (ref "R11") (pin "1") (pinfunction "1_1") (pintype "passive"))
      (node (ref "R12") (pin "1") (pinfunction "1_1") (pintype "passive"))
      (node (ref "R13") (pin "1") (pinfunction "1_1") (pintype "passive"))
      (node (ref "R16") (pin "1") (pinfunction "1_1") (pintype "passive"))
      (node (ref "R19") (pin "2") (pinfunction "2_2") (pintype "passive"))
      (node (ref "REG2") (pin "4") (pinfunction "GND_4") (pintype "power_in"))
    )
    (net (code "110") (name "Net-(C11-Pad1)") (class "Default")
      (node (ref "C11") (pin "1") (pinfunction "1_1") (pintype "passive"))
      (node (ref "R20") (pin "1") (pinfunction "1_1") (pintype "passive"))
    )
    (net (code "111") (name "Net-(D4-PadC)") (class "Default")
      (node (ref "D4") (pin "C") (pinfunction "C_C") (pintype "passive"))
      (node (ref "D5") (pin "A") (pinfunction "A_A") (pintype "passive"))
    )
    (net (code "112") (name "Net-(DECA-P$2)") (class "Default")
      (node (ref "AX1") (pin "1") (pinfunction "1_1") (pintype "passive"))
      (node (ref "DEC") (pin "AA1") (pinfunction "P$2_AA1") (pintype "bidirectional"))
      (node (ref "ECS") (pin "AA1") (pinfunction "P$2_AA1") (pintype "bidirectional"))
      (node (ref "EDAC") (pin "AA1") (pinfunction "P$2_AA1") (pintype "bidirectional"))
    )
    (net (code "113") (name "Net-(DECAA-P$2)") (class "Default")
      (node (ref "AX1") (pin "27") (pinfunction "27_27") (pintype "passive"))
      (node (ref "DEC") (pin "AR1") (pinfunction "P$2_AR1") (pintype "bidirectional"))
      (node (ref "ECS") (pin "AR1") (pinfunction "P$2_AR1") (pintype "bidirectional"))
      (node (ref "EDAC") (pin "AR1") (pinfunction "P$2_AR1") (pintype "bidirectional"))
    )
    (net (code "114") (name "Net-(DECAB-P$2)") (class "Default")
      (node (ref "AX2") (pin "27") (pinfunction "27_27") (pintype "passive"))
      (node (ref "DEC") (pin "AR2") (pinfunction "P$2_AR2") (pintype "bidirectional"))
      (node (ref "ECS") (pin "AR2") (pinfunction "P$2_AR2") (pintype "bidirectional"))
      (node (ref "EDAC") (pin "AR2") (pinfunction "P$2_AR2") (pintype "bidirectional"))
    )
    (net (code "115") (name "Net-(DECAC-P$2)") (class "Default")
      (node (ref "AX1") (pin "29") (pinfunction "29_29") (pintype "passive"))
      (node (ref "DEC") (pin "AS1") (pinfunction "P$2_AS1") (pintype "bidirectional"))
      (node (ref "ECS") (pin "AS1") (pinfunction "P$2_AS1") (pintype "bidirectional"))
      (node (ref "EDAC") (pin "AS1") (pinfunction "P$2_AS1") (pintype "bidirectional"))
    )
    (net (code "116") (name "Net-(DECAD-P$2)") (class "Default")
      (node (ref "AX2") (pin "29") (pinfunction "29_29") (pintype "passive"))
      (node (ref "DEC") (pin "AS2") (pinfunction "P$2_AS2") (pintype "bidirectional"))
      (node (ref "ECS") (pin "AS2") (pinfunction "P$2_AS2") (pintype "bidirectional"))
      (node (ref "EDAC") (pin "AS2") (pinfunction "P$2_AS2") (pintype "bidirectional"))
    )
    (net (code "117") (name "Net-(DECAE-P$2)") (class "Default")
      (node (ref "AX1") (pin "31") (pinfunction "31_31") (pintype "passive"))
      (node (ref "DEC") (pin "AT1") (pinfunction "P$2_AT1") (pintype "bidirectional"))
      (node (ref "ECS") (pin "AT1") (pinfunction "P$2_AT1") (pintype "bidirectional"))
      (node (ref "EDAC") (pin "AT1") (pinfunction "P$2_AT1") (pintype "bidirectional"))
    )
    (net (code "118") (name "Net-(DECAF-P$2)") (class "Default")
      (node (ref "AX2") (pin "31") (pinfunction "31_31") (pintype "passive"))
      (node (ref "DEC") (pin "AT2") (pinfunction "P$2_AT2") (pintype "bidirectional"))
      (node (ref "ECS") (pin "AT2") (pinfunction "P$2_AT2") (pintype "bidirectional"))
      (node (ref "EDAC") (pin "AT2") (pinfunction "P$2_AT2") (pintype "bidirectional"))
    )
    (net (code "119") (name "Net-(DECAG-P$2)") (class "Default")
      (node (ref "AX1") (pin "33") (pinfunction "33_33") (pintype "passive"))
      (node (ref "DEC") (pin "AU1") (pinfunction "P$2_AU1") (pintype "bidirectional"))
      (node (ref "ECS") (pin "AU1") (pinfunction "P$2_AU1") (pintype "bidirectional"))
      (node (ref "EDAC") (pin "AU1") (pinfunction "P$2_AU1") (pintype "bidirectional"))
    )
    (net (code "120") (name "Net-(DECAH-P$2)") (class "Default")
      (node (ref "AX2") (pin "33") (pinfunction "33_33") (pintype "passive"))
      (node (ref "DEC") (pin "AU2") (pinfunction "P$2_AU2") (pintype "bidirectional"))
      (node (ref "ECS") (pin "AU2") (pinfunction "P$2_AU2") (pintype "bidirectional"))
      (node (ref "EDAC") (pin "AU2") (pinfunction "P$2_AU2") (pintype "bidirectional"))
    )
    (net (code "121") (name "Net-(DECAI-P$2)") (class "Default")
      (node (ref "AX1") (pin "35") (pinfunction "35_35") (pintype "passive"))
      (node (ref "DEC") (pin "AV1") (pinfunction "P$2_AV1") (pintype "bidirectional"))
      (node (ref "ECS") (pin "AV1") (pinfunction "P$2_AV1") (pintype "bidirectional"))
      (node (ref "EDAC") (pin "AV1") (pinfunction "P$2_AV1") (pintype "bidirectional"))
    )
    (net (code "122") (name "Net-(DECAJ-P$2)") (class "Default")
      (node (ref "AX2") (pin "35") (pinfunction "35_35") (pintype "passive"))
      (node (ref "DEC") (pin "AV2") (pinfunction "P$2_AV2") (pintype "bidirectional"))
      (node (ref "ECS") (pin "AV2") (pinfunction "P$2_AV2") (pintype "bidirectional"))
      (node (ref "EDAC") (pin "AV2") (pinfunction "P$2_AV2") (pintype "bidirectional"))
    )
    (net (code "123") (name "Net-(DECAK-P$2)") (class "Default")
      (node (ref "BX1") (pin "1") (pinfunction "1_1") (pintype "passive"))
      (node (ref "DEC") (pin "BA1") (pinfunction "P$2_BA1") (pintype "bidirectional"))
      (node (ref "ECS") (pin "BA1") (pinfunction "P$2_BA1") (pintype "bidirectional"))
      (node (ref "EDAC") (pin "BA1") (pinfunction "P$2_BA1") (pintype "bidirectional"))
    )
    (net (code "124") (name "Net-(DECAL-P$2)") (class "Default")
      (node (ref "BX2") (pin "1") (pinfunction "1_1") (pintype "passive"))
      (node (ref "DEC") (pin "BA2") (pinfunction "P$2_BA2") (pintype "bidirectional"))
      (node (ref "ECS") (pin "BA2") (pinfunction "P$2_BA2") (pintype "bidirectional"))
      (node (ref "EDAC") (pin "BA2") (pinfunction "P$2_BA2") (pintype "bidirectional"))
    )
    (net (code "125") (name "Net-(DECAM-P$2)") (class "Default")
      (node (ref "BX1") (pin "3") (pinfunction "3_3") (pintype "passive"))
      (node (ref "DEC") (pin "BB1") (pinfunction "P$2_BB1") (pintype "bidirectional"))
      (node (ref "ECS") (pin "BB1") (pinfunction "P$2_BB1") (pintype "bidirectional"))
      (node (ref "EDAC") (pin "BB1") (pinfunction "P$2_BB1") (pintype "bidirectional"))
    )
    (net (code "126") (name "Net-(DECAN-P$2)") (class "Default")
      (node (ref "BX2") (pin "3") (pinfunction "3_3") (pintype "passive"))
      (node (ref "DEC") (pin "BB2") (pinfunction "P$2_BB2") (pintype "bidirectional"))
      (node (ref "ECS") (pin "BB2") (pinfunction "P$2_BB2") (pintype "bidirectional"))
      (node (ref "EDAC") (pin "BB2") (pinfunction "P$2_BB2") (pintype "bidirectional"))
    )
    (net (code "127") (name "Net-(DECAO-P$2)") (class "Default")
      (node (ref "BX1") (pin "5") (pinfunction "5_5") (pintype "passive"))
      (node (ref "DEC") (pin "BC1") (pinfunction "P$2_BC1") (pintype "bidirectional"))
      (node (ref "ECS") (pin "BC1") (pinfunction "P$2_BC1") (pintype "bidirectional"))
      (node (ref "EDAC") (pin "BC1") (pinfunction "P$2_BC1") (pintype "bidirectional"))
    )
    (net (code "128") (name "Net-(DECAP-P$2)") (class "Default")
      (node (ref "BX2") (pin "5") (pinfunction "5_5") (pintype "passive"))
      (node (ref "DEC") (pin "BC2") (pinfunction "P$2_BC2") (pintype "bidirectional"))
      (node (ref "ECS") (pin "BC2") (pinfunction "P$2_BC2") (pintype "bidirectional"))
      (node (ref "EDAC") (pin "BC2") (pinfunction "P$2_BC2") (pintype "bidirectional"))
    )
    (net (code "129") (name "Net-(DECAQ-P$2)") (class "Default")
      (node (ref "BX1") (pin "7") (pinfunction "7_7") (pintype "passive"))
      (node (ref "DEC") (pin "BD1") (pinfunction "P$2_BD1") (pintype "bidirectional"))
      (node (ref "ECS") (pin "BD1") (pinfunction "P$2_BD1") (pintype "bidirectional"))
      (node (ref "EDAC") (pin "BD1") (pinfunction "P$2_BD1") (pintype "bidirectional"))
    )
    (net (code "130") (name "Net-(DECAR-P$2)") (class "Default")
      (node (ref "BX2") (pin "7") (pinfunction "7_7") (pintype "passive"))
      (node (ref "DEC") (pin "BD2") (pinfunction "P$2_BD2") (pintype "bidirectional"))
      (node (ref "ECS") (pin "BD2") (pinfunction "P$2_BD2") (pintype "bidirectional"))
      (node (ref "EDAC") (pin "BD2") (pinfunction "P$2_BD2") (pintype "bidirectional"))
    )
    (net (code "131") (name "Net-(DECAS-P$2)") (class "Default")
      (node (ref "BX1") (pin "9") (pinfunction "9_9") (pintype "passive"))
      (node (ref "DEC") (pin "BE1") (pinfunction "P$2_BE1") (pintype "bidirectional"))
      (node (ref "ECS") (pin "BE1") (pinfunction "P$2_BE1") (pintype "bidirectional"))
      (node (ref "EDAC") (pin "BE1") (pinfunction "P$2_BE1") (pintype "bidirectional"))
    )
    (net (code "132") (name "Net-(DECAT-P$2)") (class "Default")
      (node (ref "BX2") (pin "9") (pinfunction "9_9") (pintype "passive"))
      (node (ref "DEC") (pin "BE2") (pinfunction "P$2_BE2") (pintype "bidirectional"))
      (node (ref "ECS") (pin "BE2") (pinfunction "P$2_BE2") (pintype "bidirectional"))
      (node (ref "EDAC") (pin "BE2") (pinfunction "P$2_BE2") (pintype "bidirectional"))
    )
    (net (code "133") (name "Net-(DECAU-P$2)") (class "Default")
      (node (ref "BX1") (pin "11") (pinfunction "11_11") (pintype "passive"))
      (node (ref "DEC") (pin "BF1") (pinfunction "P$2_BF1") (pintype "bidirectional"))
      (node (ref "ECS") (pin "BF1") (pinfunction "P$2_BF1") (pintype "bidirectional"))
      (node (ref "EDAC") (pin "BF1") (pinfunction "P$2_BF1") (pintype "bidirectional"))
    )
    (net (code "134") (name "Net-(DECAV-P$2)") (class "Default")
      (node (ref "BX2") (pin "11") (pinfunction "11_11") (pintype "passive"))
      (node (ref "DEC") (pin "BF2") (pinfunction "P$2_BF2") (pintype "bidirectional"))
      (node (ref "ECS") (pin "BF2") (pinfunction "P$2_BF2") (pintype "bidirectional"))
      (node (ref "EDAC") (pin "BF2") (pinfunction "P$2_BF2") (pintype "bidirectional"))
    )
    (net (code "135") (name "Net-(DECAW-P$2)") (class "Default")
      (node (ref "BX1") (pin "13") (pinfunction "13_13") (pintype "passive"))
      (node (ref "DEC") (pin "BH1") (pinfunction "P$2_BH1") (pintype "bidirectional"))
      (node (ref "ECS") (pin "BH1") (pinfunction "P$2_BH1") (pintype "bidirectional"))
      (node (ref "EDAC") (pin "BH1") (pinfunction "P$2_BH1") (pintype "bidirectional"))
    )
    (net (code "136") (name "Net-(DECAX-P$2)") (class "Default")
      (node (ref "BX2") (pin "13") (pinfunction "13_13") (pintype "passive"))
      (node (ref "DEC") (pin "BH2") (pinfunction "P$2_BH2") (pintype "bidirectional"))
      (node (ref "ECS") (pin "BH2") (pinfunction "P$2_BH2") (pintype "bidirectional"))
      (node (ref "EDAC") (pin "BH2") (pinfunction "P$2_BH2") (pintype "bidirectional"))
    )
    (net (code "137") (name "Net-(DECAY-P$2)") (class "Default")
      (node (ref "BX1") (pin "15") (pinfunction "15_15") (pintype "passive"))
      (node (ref "DEC") (pin "BJ1") (pinfunction "P$2_BJ1") (pintype "bidirectional"))
      (node (ref "ECS") (pin "BJ1") (pinfunction "P$2_BJ1") (pintype "bidirectional"))
      (node (ref "EDAC") (pin "BJ1") (pinfunction "P$2_BJ1") (pintype "bidirectional"))
    )
    (net (code "138") (name "Net-(DECAZ-P$2)") (class "Default")
      (node (ref "BX2") (pin "15") (pinfunction "15_15") (pintype "passive"))
      (node (ref "DEC") (pin "BJ2") (pinfunction "P$2_BJ2") (pintype "bidirectional"))
      (node (ref "ECS") (pin "BJ2") (pinfunction "P$2_BJ2") (pintype "bidirectional"))
      (node (ref "EDAC") (pin "BJ2") (pinfunction "P$2_BJ2") (pintype "bidirectional"))
    )
    (net (code "139") (name "Net-(DECB-P$2)") (class "Default")
      (node (ref "AX2") (pin "1") (pinfunction "1_1") (pintype "passive"))
      (node (ref "DEC") (pin "AA2") (pinfunction "P$2_AA2") (pintype "bidirectional"))
      (node (ref "ECS") (pin "AA2") (pinfunction "P$2_AA2") (pintype "bidirectional"))
      (node (ref "EDAC") (pin "AA2") (pinfunction "P$2_AA2") (pintype "bidirectional"))
    )
    (net (code "140") (name "Net-(DECBA-P$2)") (class "Default")
      (node (ref "BX1") (pin "17") (pinfunction "17_17") (pintype "passive"))
      (node (ref "DEC") (pin "BK1") (pinfunction "P$2_BK1") (pintype "bidirectional"))
      (node (ref "ECS") (pin "BK1") (pinfunction "P$2_BK1") (pintype "bidirectional"))
      (node (ref "EDAC") (pin "BK1") (pinfunction "P$2_BK1") (pintype "bidirectional"))
    )
    (net (code "141") (name "Net-(DECBB-P$2)") (class "Default")
      (node (ref "BX2") (pin "17") (pinfunction "17_17") (pintype "passive"))
      (node (ref "DEC") (pin "BK2") (pinfunction "P$2_BK2") (pintype "bidirectional"))
      (node (ref "ECS") (pin "BK2") (pinfunction "P$2_BK2") (pintype "bidirectional"))
      (node (ref "EDAC") (pin "BK2") (pinfunction "P$2_BK2") (pintype "bidirectional"))
    )
    (net (code "142") (name "Net-(DECBC-P$2)") (class "Default")
      (node (ref "BX1") (pin "19") (pinfunction "19_19") (pintype "passive"))
      (node (ref "DEC") (pin "BL1") (pinfunction "P$2_BL1") (pintype "bidirectional"))
      (node (ref "ECS") (pin "BL1") (pinfunction "P$2_BL1") (pintype "bidirectional"))
      (node (ref "EDAC") (pin "BL1") (pinfunction "P$2_BL1") (pintype "bidirectional"))
    )
    (net (code "143") (name "Net-(DECBD-P$2)") (class "Default")
      (node (ref "BX2") (pin "19") (pinfunction "19_19") (pintype "passive"))
      (node (ref "DEC") (pin "BL2") (pinfunction "P$2_BL2") (pintype "bidirectional"))
      (node (ref "ECS") (pin "BL2") (pinfunction "P$2_BL2") (pintype "bidirectional"))
      (node (ref "EDAC") (pin "BL2") (pinfunction "P$2_BL2") (pintype "bidirectional"))
    )
    (net (code "144") (name "Net-(DECBE-P$2)") (class "Default")
      (node (ref "BX1") (pin "21") (pinfunction "21_21") (pintype "passive"))
      (node (ref "DEC") (pin "BM1") (pinfunction "P$2_BM1") (pintype "bidirectional"))
      (node (ref "ECS") (pin "BM1") (pinfunction "P$2_BM1") (pintype "bidirectional"))
      (node (ref "EDAC") (pin "BM1") (pinfunction "P$2_BM1") (pintype "bidirectional"))
    )
    (net (code "145") (name "Net-(DECBF-P$2)") (class "Default")
      (node (ref "BX2") (pin "21") (pinfunction "21_21") (pintype "passive"))
      (node (ref "DEC") (pin "BM2") (pinfunction "P$2_BM2") (pintype "bidirectional"))
      (node (ref "ECS") (pin "BM2") (pinfunction "P$2_BM2") (pintype "bidirectional"))
      (node (ref "EDAC") (pin "BM2") (pinfunction "P$2_BM2") (pintype "bidirectional"))
    )
    (net (code "146") (name "Net-(DECBG-P$2)") (class "Default")
      (node (ref "BX1") (pin "23") (pinfunction "23_23") (pintype "passive"))
      (node (ref "DEC") (pin "BN1") (pinfunction "P$2_BN1") (pintype "bidirectional"))
      (node (ref "ECS") (pin "BN1") (pinfunction "P$2_BN1") (pintype "bidirectional"))
      (node (ref "EDAC") (pin "BN1") (pinfunction "P$2_BN1") (pintype "bidirectional"))
    )
    (net (code "147") (name "Net-(DECBH-P$2)") (class "Default")
      (node (ref "BX2") (pin "23") (pinfunction "23_23") (pintype "passive"))
      (node (ref "DEC") (pin "BN2") (pinfunction "P$2_BN2") (pintype "bidirectional"))
      (node (ref "ECS") (pin "BN2") (pinfunction "P$2_BN2") (pintype "bidirectional"))
      (node (ref "EDAC") (pin "BN2") (pinfunction "P$2_BN2") (pintype "bidirectional"))
    )
    (net (code "148") (name "Net-(DECBI-P$2)") (class "Default")
      (node (ref "BX1") (pin "25") (pinfunction "25_25") (pintype "passive"))
      (node (ref "DEC") (pin "BP1") (pinfunction "P$2_BP1") (pintype "bidirectional"))
      (node (ref "ECS") (pin "BP1") (pinfunction "P$2_BP1") (pintype "bidirectional"))
      (node (ref "EDAC") (pin "BP1") (pinfunction "P$2_BP1") (pintype "bidirectional"))
    )
    (net (code "149") (name "Net-(DECBJ-P$2)") (class "Default")
      (node (ref "BX2") (pin "25") (pinfunction "25_25") (pintype "passive"))
      (node (ref "DEC") (pin "BP2") (pinfunction "P$2_BP2") (pintype "bidirectional"))
      (node (ref "ECS") (pin "BP2") (pinfunction "P$2_BP2") (pintype "bidirectional"))
      (node (ref "EDAC") (pin "BP2") (pinfunction "P$2_BP2") (pintype "bidirectional"))
    )
    (net (code "150") (name "Net-(DECBK-P$2)") (class "Default")
      (node (ref "BX1") (pin "27") (pinfunction "27_27") (pintype "passive"))
      (node (ref "DEC") (pin "BR1") (pinfunction "P$2_BR1") (pintype "bidirectional"))
      (node (ref "ECS") (pin "BR1") (pinfunction "P$2_BR1") (pintype "bidirectional"))
      (node (ref "EDAC") (pin "BR1") (pinfunction "P$2_BR1") (pintype "bidirectional"))
    )
    (net (code "151") (name "Net-(DECBL-P$2)") (class "Default")
      (node (ref "BX2") (pin "27") (pinfunction "27_27") (pintype "passive"))
      (node (ref "DEC") (pin "BR2") (pinfunction "P$2_BR2") (pintype "bidirectional"))
      (node (ref "ECS") (pin "BR2") (pinfunction "P$2_BR2") (pintype "bidirectional"))
      (node (ref "EDAC") (pin "BR2") (pinfunction "P$2_BR2") (pintype "bidirectional"))
    )
    (net (code "152") (name "Net-(DECBM-P$2)") (class "Default")
      (node (ref "BX1") (pin "29") (pinfunction "29_29") (pintype "passive"))
      (node (ref "DEC") (pin "BS1") (pinfunction "P$2_BS1") (pintype "bidirectional"))
      (node (ref "ECS") (pin "BS1") (pinfunction "P$2_BS1") (pintype "bidirectional"))
      (node (ref "EDAC") (pin "BS1") (pinfunction "P$2_BS1") (pintype "bidirectional"))
    )
    (net (code "153") (name "Net-(DECBN-P$2)") (class "Default")
      (node (ref "BX2") (pin "29") (pinfunction "29_29") (pintype "passive"))
      (node (ref "DEC") (pin "BS2") (pinfunction "P$2_BS2") (pintype "bidirectional"))
      (node (ref "ECS") (pin "BS2") (pinfunction "P$2_BS2") (pintype "bidirectional"))
      (node (ref "EDAC") (pin "BS2") (pinfunction "P$2_BS2") (pintype "bidirectional"))
    )
    (net (code "154") (name "Net-(DECBO-P$2)") (class "Default")
      (node (ref "BX1") (pin "31") (pinfunction "31_31") (pintype "passive"))
      (node (ref "DEC") (pin "BT1") (pinfunction "P$2_BT1") (pintype "bidirectional"))
      (node (ref "ECS") (pin "BT1") (pinfunction "P$2_BT1") (pintype "bidirectional"))
      (node (ref "EDAC") (pin "BT1") (pinfunction "P$2_BT1") (pintype "bidirectional"))
    )
    (net (code "155") (name "Net-(DECBP-P$2)") (class "Default")
      (node (ref "BX2") (pin "31") (pinfunction "31_31") (pintype "passive"))
      (node (ref "DEC") (pin "BT2") (pinfunction "P$2_BT2") (pintype "bidirectional"))
      (node (ref "ECS") (pin "BT2") (pinfunction "P$2_BT2") (pintype "bidirectional"))
      (node (ref "EDAC") (pin "BT2") (pinfunction "P$2_BT2") (pintype "bidirectional"))
    )
    (net (code "156") (name "Net-(DECBQ-P$2)") (class "Default")
      (node (ref "BX1") (pin "33") (pinfunction "33_33") (pintype "passive"))
      (node (ref "DEC") (pin "BU1") (pinfunction "P$2_BU1") (pintype "bidirectional"))
      (node (ref "ECS") (pin "BU1") (pinfunction "P$2_BU1") (pintype "bidirectional"))
      (node (ref "EDAC") (pin "BU1") (pinfunction "P$2_BU1") (pintype "bidirectional"))
    )
    (net (code "157") (name "Net-(DECBR-P$2)") (class "Default")
      (node (ref "BX2") (pin "33") (pinfunction "33_33") (pintype "passive"))
      (node (ref "DEC") (pin "BU2") (pinfunction "P$2_BU2") (pintype "bidirectional"))
      (node (ref "ECS") (pin "BU2") (pinfunction "P$2_BU2") (pintype "bidirectional"))
      (node (ref "EDAC") (pin "BU2") (pinfunction "P$2_BU2") (pintype "bidirectional"))
    )
    (net (code "158") (name "Net-(DECBS-P$2)") (class "Default")
      (node (ref "BX1") (pin "35") (pinfunction "35_35") (pintype "passive"))
      (node (ref "DEC") (pin "BV1") (pinfunction "P$2_BV1") (pintype "bidirectional"))
      (node (ref "ECS") (pin "BV1") (pinfunction "P$2_BV1") (pintype "bidirectional"))
      (node (ref "EDAC") (pin "BV1") (pinfunction "P$2_BV1") (pintype "bidirectional"))
    )
    (net (code "159") (name "Net-(DECBT-P$2)") (class "Default")
      (node (ref "BX2") (pin "35") (pinfunction "35_35") (pintype "passive"))
      (node (ref "DEC") (pin "BV2") (pinfunction "P$2_BV2") (pintype "bidirectional"))
      (node (ref "ECS") (pin "BV2") (pinfunction "P$2_BV2") (pintype "bidirectional"))
      (node (ref "EDAC") (pin "BV2") (pinfunction "P$2_BV2") (pintype "bidirectional"))
    )
    (net (code "160") (name "Net-(DECC-P$2)") (class "Default")
      (node (ref "AX1") (pin "3") (pinfunction "3_3") (pintype "passive"))
      (node (ref "DEC") (pin "AB1") (pinfunction "P$2_AB1") (pintype "bidirectional"))
      (node (ref "ECS") (pin "AB1") (pinfunction "P$2_AB1") (pintype "bidirectional"))
      (node (ref "EDAC") (pin "AB1") (pinfunction "P$2_AB1") (pintype "bidirectional"))
    )
    (net (code "161") (name "Net-(DECD-P$2)") (class "Default")
      (node (ref "AX2") (pin "3") (pinfunction "3_3") (pintype "passive"))
      (node (ref "DEC") (pin "AB2") (pinfunction "P$2_AB2") (pintype "bidirectional"))
      (node (ref "ECS") (pin "AB2") (pinfunction "P$2_AB2") (pintype "bidirectional"))
      (node (ref "EDAC") (pin "AB2") (pinfunction "P$2_AB2") (pintype "bidirectional"))
    )
    (net (code "162") (name "Net-(DECE-P$2)") (class "Default")
      (node (ref "AX1") (pin "5") (pinfunction "5_5") (pintype "passive"))
      (node (ref "DEC") (pin "AC1") (pinfunction "P$2_AC1") (pintype "bidirectional"))
      (node (ref "ECS") (pin "AC1") (pinfunction "P$2_AC1") (pintype "bidirectional"))
      (node (ref "EDAC") (pin "AC1") (pinfunction "P$2_AC1") (pintype "bidirectional"))
    )
    (net (code "163") (name "Net-(DECF-P$2)") (class "Default")
      (node (ref "AX2") (pin "5") (pinfunction "5_5") (pintype "passive"))
      (node (ref "DEC") (pin "AC2") (pinfunction "P$2_AC2") (pintype "bidirectional"))
      (node (ref "ECS") (pin "AC2") (pinfunction "P$2_AC2") (pintype "bidirectional"))
      (node (ref "EDAC") (pin "AC2") (pinfunction "P$2_AC2") (pintype "bidirectional"))
    )
    (net (code "164") (name "Net-(DECG-P$2)") (class "Default")
      (node (ref "AX1") (pin "7") (pinfunction "7_7") (pintype "passive"))
      (node (ref "DEC") (pin "AD1") (pinfunction "P$2_AD1") (pintype "bidirectional"))
      (node (ref "ECS") (pin "AD1") (pinfunction "P$2_AD1") (pintype "bidirectional"))
      (node (ref "EDAC") (pin "AD1") (pinfunction "P$2_AD1") (pintype "bidirectional"))
    )
    (net (code "165") (name "Net-(DECH-P$2)") (class "Default")
      (node (ref "AX2") (pin "7") (pinfunction "7_7") (pintype "passive"))
      (node (ref "DEC") (pin "AD2") (pinfunction "P$2_AD2") (pintype "bidirectional"))
      (node (ref "ECS") (pin "AD2") (pinfunction "P$2_AD2") (pintype "bidirectional"))
      (node (ref "EDAC") (pin "AD2") (pinfunction "P$2_AD2") (pintype "bidirectional"))
    )
    (net (code "166") (name "Net-(DECI-P$2)") (class "Default")
      (node (ref "AX1") (pin "9") (pinfunction "9_9") (pintype "passive"))
      (node (ref "DEC") (pin "AE1") (pinfunction "P$2_AE1") (pintype "bidirectional"))
      (node (ref "ECS") (pin "AE1") (pinfunction "P$2_AE1") (pintype "bidirectional"))
      (node (ref "EDAC") (pin "AE1") (pinfunction "P$2_AE1") (pintype "bidirectional"))
    )
    (net (code "167") (name "Net-(DECJ-P$2)") (class "Default")
      (node (ref "AX2") (pin "9") (pinfunction "9_9") (pintype "passive"))
      (node (ref "DEC") (pin "AE2") (pinfunction "P$2_AE2") (pintype "bidirectional"))
      (node (ref "ECS") (pin "AE2") (pinfunction "P$2_AE2") (pintype "bidirectional"))
      (node (ref "EDAC") (pin "AE2") (pinfunction "P$2_AE2") (pintype "bidirectional"))
    )
    (net (code "168") (name "Net-(DECK-P$2)") (class "Default")
      (node (ref "AX1") (pin "11") (pinfunction "11_11") (pintype "passive"))
      (node (ref "DEC") (pin "AF1") (pinfunction "P$2_AF1") (pintype "bidirectional"))
      (node (ref "ECS") (pin "AF1") (pinfunction "P$2_AF1") (pintype "bidirectional"))
      (node (ref "EDAC") (pin "AF1") (pinfunction "P$2_AF1") (pintype "bidirectional"))
    )
    (net (code "169") (name "Net-(DECL-P$2)") (class "Default")
      (node (ref "AX2") (pin "11") (pinfunction "11_11") (pintype "passive"))
      (node (ref "DEC") (pin "AF2") (pinfunction "P$2_AF2") (pintype "bidirectional"))
      (node (ref "ECS") (pin "AF2") (pinfunction "P$2_AF2") (pintype "bidirectional"))
      (node (ref "EDAC") (pin "AF2") (pinfunction "P$2_AF2") (pintype "bidirectional"))
    )
    (net (code "170") (name "Net-(DECM-P$2)") (class "Default")
      (node (ref "AX1") (pin "13") (pinfunction "13_13") (pintype "passive"))
      (node (ref "DEC") (pin "AH1") (pinfunction "P$2_AH1") (pintype "bidirectional"))
      (node (ref "ECS") (pin "AH1") (pinfunction "P$2_AH1") (pintype "bidirectional"))
      (node (ref "EDAC") (pin "AH1") (pinfunction "P$2_AH1") (pintype "bidirectional"))
    )
    (net (code "171") (name "Net-(DECN-P$2)") (class "Default")
      (node (ref "AX2") (pin "13") (pinfunction "13_13") (pintype "passive"))
      (node (ref "DEC") (pin "AH2") (pinfunction "P$2_AH2") (pintype "bidirectional"))
      (node (ref "ECS") (pin "AH2") (pinfunction "P$2_AH2") (pintype "bidirectional"))
      (node (ref "EDAC") (pin "AH2") (pinfunction "P$2_AH2") (pintype "bidirectional"))
    )
    (net (code "172") (name "Net-(DECO-P$2)") (class "Default")
      (node (ref "AX1") (pin "15") (pinfunction "15_15") (pintype "passive"))
      (node (ref "DEC") (pin "AJ1") (pinfunction "P$2_AJ1") (pintype "bidirectional"))
      (node (ref "ECS") (pin "AJ1") (pinfunction "P$2_AJ1") (pintype "bidirectional"))
      (node (ref "EDAC") (pin "AJ1") (pinfunction "P$2_AJ1") (pintype "bidirectional"))
    )
    (net (code "173") (name "Net-(DECP-P$2)") (class "Default")
      (node (ref "AX2") (pin "15") (pinfunction "15_15") (pintype "passive"))
      (node (ref "DEC") (pin "AJ2") (pinfunction "P$2_AJ2") (pintype "bidirectional"))
      (node (ref "ECS") (pin "AJ2") (pinfunction "P$2_AJ2") (pintype "bidirectional"))
      (node (ref "EDAC") (pin "AJ2") (pinfunction "P$2_AJ2") (pintype "bidirectional"))
    )
    (net (code "174") (name "Net-(DECQ-P$2)") (class "Default")
      (node (ref "AX1") (pin "17") (pinfunction "17_17") (pintype "passive"))
      (node (ref "DEC") (pin "AK1") (pinfunction "P$2_AK1") (pintype "bidirectional"))
      (node (ref "ECS") (pin "AK1") (pinfunction "P$2_AK1") (pintype "bidirectional"))
      (node (ref "EDAC") (pin "AK1") (pinfunction "P$2_AK1") (pintype "bidirectional"))
    )
    (net (code "175") (name "Net-(DECR-P$2)") (class "Default")
      (node (ref "AX2") (pin "17") (pinfunction "17_17") (pintype "passive"))
      (node (ref "DEC") (pin "AK2") (pinfunction "P$2_AK2") (pintype "bidirectional"))
      (node (ref "ECS") (pin "AK2") (pinfunction "P$2_AK2") (pintype "bidirectional"))
      (node (ref "EDAC") (pin "AK2") (pinfunction "P$2_AK2") (pintype "bidirectional"))
    )
    (net (code "176") (name "Net-(DECS-P$2)") (class "Default")
      (node (ref "AX1") (pin "19") (pinfunction "19_19") (pintype "passive"))
      (node (ref "DEC") (pin "AL1") (pinfunction "P$2_AL1") (pintype "bidirectional"))
      (node (ref "ECS") (pin "AL1") (pinfunction "P$2_AL1") (pintype "bidirectional"))
      (node (ref "EDAC") (pin "AL1") (pinfunction "P$2_AL1") (pintype "bidirectional"))
    )
    (net (code "177") (name "Net-(DECT-P$2)") (class "Default")
      (node (ref "AX2") (pin "19") (pinfunction "19_19") (pintype "passive"))
      (node (ref "DEC") (pin "AL2") (pinfunction "P$2_AL2") (pintype "bidirectional"))
      (node (ref "ECS") (pin "AL2") (pinfunction "P$2_AL2") (pintype "bidirectional"))
      (node (ref "EDAC") (pin "AL2") (pinfunction "P$2_AL2") (pintype "bidirectional"))
    )
    (net (code "178") (name "Net-(DECU-P$2)") (class "Default")
      (node (ref "AX1") (pin "21") (pinfunction "21_21") (pintype "passive"))
      (node (ref "DEC") (pin "AM1") (pinfunction "P$2_AM1") (pintype "bidirectional"))
      (node (ref "ECS") (pin "AM1") (pinfunction "P$2_AM1") (pintype "bidirectional"))
      (node (ref "EDAC") (pin "AM1") (pinfunction "P$2_AM1") (pintype "bidirectional"))
    )
    (net (code "179") (name "Net-(DECV-P$2)") (class "Default")
      (node (ref "AX2") (pin "21") (pinfunction "21_21") (pintype "passive"))
      (node (ref "DEC") (pin "AM2") (pinfunction "P$2_AM2") (pintype "bidirectional"))
      (node (ref "ECS") (pin "AM2") (pinfunction "P$2_AM2") (pintype "bidirectional"))
      (node (ref "EDAC") (pin "AM2") (pinfunction "P$2_AM2") (pintype "bidirectional"))
    )
    (net (code "180") (name "Net-(DECW-P$2)") (class "Default")
      (node (ref "AX1") (pin "23") (pinfunction "23_23") (pintype "passive"))
      (node (ref "DEC") (pin "AN1") (pinfunction "P$2_AN1") (pintype "bidirectional"))
      (node (ref "ECS") (pin "AN1") (pinfunction "P$2_AN1") (pintype "bidirectional"))
      (node (ref "EDAC") (pin "AN1") (pinfunction "P$2_AN1") (pintype "bidirectional"))
    )
    (net (code "181") (name "Net-(DECX-P$2)") (class "Default")
      (node (ref "AX2") (pin "23") (pinfunction "23_23") (pintype "passive"))
      (node (ref "DEC") (pin "AN2") (pinfunction "P$2_AN2") (pintype "bidirectional"))
      (node (ref "ECS") (pin "AN2") (pinfunction "P$2_AN2") (pintype "bidirectional"))
      (node (ref "EDAC") (pin "AN2") (pinfunction "P$2_AN2") (pintype "bidirectional"))
    )
    (net (code "182") (name "Net-(DECY-P$2)") (class "Default")
      (node (ref "AX1") (pin "25") (pinfunction "25_25") (pintype "passive"))
      (node (ref "DEC") (pin "AP1") (pinfunction "P$2_AP1") (pintype "bidirectional"))
      (node (ref "ECS") (pin "AP1") (pinfunction "P$2_AP1") (pintype "bidirectional"))
      (node (ref "EDAC") (pin "AP1") (pinfunction "P$2_AP1") (pintype "bidirectional"))
    )
    (net (code "183") (name "Net-(DECZ-P$2)") (class "Default")
      (node (ref "AX2") (pin "25") (pinfunction "25_25") (pintype "passive"))
      (node (ref "DEC") (pin "AP2") (pinfunction "P$2_AP2") (pintype "bidirectional"))
      (node (ref "ECS") (pin "AP2") (pinfunction "P$2_AP2") (pintype "bidirectional"))
      (node (ref "EDAC") (pin "AP2") (pinfunction "P$2_AP2") (pintype "bidirectional"))
    )
    (net (code "184") (name "Net-(GREEN-C)") (class "Default")
      (node (ref "GREEN") (pin "K") (pinfunction "C_K") (pintype "passive"))
      (node (ref "R2") (pin "2") (pinfunction "2_2") (pintype "passive"))
    )
    (net (code "185") (name "Net-(IC1-GPA7)") (class "Default")
      (node (ref "IC1") (pin "28") (pinfunction "GPA7_28") (pintype "bidirectional"))
      (node (ref "R1") (pin "1") (pinfunction "1_1") (pintype "passive"))
    )
    (net (code "186") (name "Net-(IC3-GPA2)") (class "Default")
      (node (ref "IC3") (pin "23") (pinfunction "GPA2_23") (pintype "bidirectional"))
      (node (ref "R15") (pin "1") (pinfunction "1_1") (pintype "passive"))
    )
    (net (code "187") (name "Net-(J2E-S)") (class "Default")
      (node (ref "J2") (pin "5") (pinfunction "S_5") (pintype "passive"))
      (node (ref "UUT") (pin "5") (pinfunction "B2_5") (pintype "bidirectional"))
    )
    (net (code "188") (name "Net-(LOADHI1-Pad1)") (class "Default")
      (node (ref "LOADHI1") (pin "1") (pinfunction "1_1") (pintype "passive"))
      (node (ref "R11") (pin "2") (pinfunction "2_2") (pintype "passive"))
    )
    (net (code "189") (name "Net-(LOADHI3-Pad1)") (class "Default")
      (node (ref "LOADHI3") (pin "1") (pinfunction "1_1") (pintype "passive"))
      (node (ref "R10") (pin "2") (pinfunction "2_2") (pintype "passive"))
    )
    (net (code "190") (name "Net-(LOADL1-Pad1)") (class "Default")
      (node (ref "LOADL1") (pin "1") (pinfunction "1_1") (pintype "passive"))
      (node (ref "R8") (pin "1") (pinfunction "1_1") (pintype "passive"))
      (node (ref "R9") (pin "1") (pinfunction "1_1") (pintype "passive"))
    )
    (net (code "191") (name "Net-(LOADL3-Pad1)") (class "Default")
      (node (ref "LOADL3") (pin "1") (pinfunction "1_1") (pintype "passive"))
      (node (ref "R6") (pin "1") (pinfunction "1_1") (pintype "passive"))
      (node (ref "R7") (pin "1") (pinfunction "1_1") (pintype "passive"))
    )
    (net (code "192") (name "Net-(PWR-C)") (class "Default")
      (node (ref "PWR") (pin "K") (pinfunction "C_K") (pintype "passive"))
      (node (ref "R14") (pin "2") (pinfunction "2_2") (pintype "passive"))
    )
    (net (code "193") (name "Net-(RED1-C)") (class "Default")
      (node (ref "R3") (pin "2") (pinfunction "2_2") (pintype "passive"))
      (node (ref "RED1") (pin "K") (pinfunction "C_K") (pintype "passive"))
    )
    (net (code "194") (name "Net-(RED2-C)") (class "Default")
      (node (ref "R5") (pin "2") (pinfunction "2_2") (pintype "passive"))
      (node (ref "RED2") (pin "K") (pinfunction "C_K") (pintype "passive"))
    )
    (net (code "195") (name "Net-(REG1-ADJ)") (class "Default")
      (node (ref "R22") (pin "1") (pinfunction "1_1") (pintype "passive"))
      (node (ref "R23") (pin "2") (pinfunction "2_2") (pintype "passive"))
      (node (ref "REG1") (pin "1") (pinfunction "ADJ_1") (pintype "input"))
    )
    (net (code "196") (name "Net-(REG2-DC)") (class "Default")
      (node (ref "R18") (pin "2") (pinfunction "2_2") (pintype "passive"))
      (node (ref "REG2") (pin "1") (pinfunction "SWC_1") (pintype "input"))
      (node (ref "REG2") (pin "7") (pinfunction "IPK_7") (pintype "bidirectional"))
      (node (ref "REG2") (pin "8") (pinfunction "DC_8") (pintype "input"))
    )
    (net (code "197") (name "Net-(REG2-SWE)") (class "Default")
      (node (ref "D1") (pin "C") (pinfunction "C_C") (pintype "passive"))
      (node (ref "L2") (pin "1") (pinfunction "1_1") (pintype "passive"))
      (node (ref "REG2") (pin "2") (pinfunction "SWE_2") (pintype "input"))
    )
    (net (code "198") (name "Net-(REG2-TC)") (class "Default")
      (node (ref "C8") (pin "1") (pinfunction "1_1") (pintype "passive"))
      (node (ref "REG2") (pin "3") (pinfunction "TC_3") (pintype "input"))
    )
    (net (code "199") (name "Net-(REG3-COMP)") (class "Default")
      (node (ref "C11") (pin "2") (pinfunction "2_2") (pintype "passive"))
      (node (ref "REG3") (pin "5") (pinfunction "COMP_5") (pintype "input"))
    )
    (net (code "200") (name "Net-(REG3-FI)") (class "Default")
      (node (ref "C10") (pin "1") (pinfunction "1_1") (pintype "passive"))
      (node (ref "R19") (pin "1") (pinfunction "1_1") (pintype "passive"))
      (node (ref "R20") (pin "2") (pinfunction "2_2") (pintype "passive"))
      (node (ref "R21") (pin "1") (pinfunction "1_1") (pintype "passive"))
      (node (ref "REG3") (pin "1") (pinfunction "FI_1") (pintype "input"))
    )
    (net (code "201") (name "Net-(REG3-OUT)") (class "Default")
      (node (ref "D2") (pin "C") (pinfunction "C_C") (pintype "passive"))
      (node (ref "L1") (pin "1") (pinfunction "1_1") (pintype "passive"))
      (node (ref "REG3") (pin "2") (pinfunction "OUT_2") (pintype "output"))
    )
    (net (code "202") (name "Net-(UUT_PWR-C)") (class "Default")
      (node (ref "R12") (pin "2") (pinfunction "2_2") (pintype "passive"))
      (node (ref "R13") (pin "2") (pinfunction "2_2") (pintype "passive"))
      (node (ref "UUT_PWR") (pin "K") (pinfunction "C_K") (pintype "passive"))
    )
    (net (code "203") (name "Net-(YELLOW-C)") (class "Default")
      (node (ref "R4") (pin "2") (pinfunction "2_2") (pintype "passive"))
      (node (ref "YELLOW") (pin "K") (pinfunction "C_K") (pintype "passive"))
    )
    (net (code "204") (name "V+") (class "Default")
      (node (ref "AX2") (pin "2") (pinfunction "2_2") (pintype "passive"))
      (node (ref "BX2") (pin "2") (pinfunction "2_2") (pintype "passive"))
      (node (ref "R1") (pin "2") (pinfunction "2_2") (pintype "passive"))
      (node (ref "R15") (pin "2") (pinfunction "2_2") (pintype "passive"))
      (node (ref "R6") (pin "2") (pinfunction "2_2") (pintype "passive"))
      (node (ref "R7") (pin "2") (pinfunction "2_2") (pintype "passive"))
      (node (ref "R8") (pin "2") (pinfunction "2_2") (pintype "passive"))
      (node (ref "R9") (pin "2") (pinfunction "2_2") (pintype "passive"))
      (node (ref "UUT") (pin "6") (pinfunction "B3_6") (pintype "bidirectional"))
      (node (ref "UUT_PWR") (pin "A") (pinfunction "A_A") (pintype "passive"))
      (node (ref "V+") (pin "1") (pinfunction "1_1") (pintype "passive"))
      (node (ref "V+") (pin "2") (pinfunction "2_2") (pintype "passive"))
      (node (ref "V+") (pin "3") (pinfunction "3_3") (pintype "passive"))
      (node (ref "V+") (pin "4") (pinfunction "4_4") (pintype "passive"))
      (node (ref "V+") (pin "5") (pinfunction "5_5") (pintype "passive"))
      (node (ref "V+") (pin "6") (pinfunction "6_6") (pintype "passive"))
      (node (ref "V+") (pin "7") (pinfunction "7_7") (pintype "passive"))
      (node (ref "V+") (pin "8") (pinfunction "8_8") (pintype "passive"))
      (node (ref "VPP0") (pin "1") (pinfunction "1_1") (pintype "passive"))
    )
    (net (code "205") (name "V-") (class "Default")
      (node (ref "-V") (pin "1") (pinfunction "1_1") (pintype "passive"))
      (node (ref "SV1") (pin "1") (pinfunction "1_1") (pintype "passive"))
      (node (ref "SV2") (pin "1") (pinfunction "1_1") (pintype "passive"))
      (node (ref "UUT") (pin "3") (pinfunction "A3_3") (pintype "bidirectional"))
      (node (ref "V-") (pin "1") (pinfunction "1_1") (pintype "passive"))
      (node (ref "V-") (pin "2") (pinfunction "2_2") (pintype "passive"))
      (node (ref "V-") (pin "3") (pinfunction "3_3") (pintype "passive"))
      (node (ref "V-") (pin "4") (pinfunction "4_4") (pintype "passive"))
      (node (ref "V-") (pin "5") (pinfunction "5_5") (pintype "passive"))
      (node (ref "V-") (pin "6") (pinfunction "6_6") (pintype "passive"))
      (node (ref "V-") (pin "7") (pinfunction "7_7") (pintype "passive"))
      (node (ref "V-") (pin "8") (pinfunction "8_8") (pintype "passive"))
    )
    (net (code "206") (name "VCC") (class "Default")
      (node (ref "C1") (pin "+") (pinfunction "+_+") (pintype "passive"))
      (node (ref "D4") (pin "A") (pinfunction "A_A") (pintype "passive"))
      (node (ref "J2") (pin "4") (pinfunction "S_4") (pintype "passive"))
      (node (ref "R22") (pin "2") (pinfunction "2_2") (pintype "passive"))
      (node (ref "RASPI") (pin "2") (pinfunction "2_2") (pintype "passive"))
      (node (ref "RASPI") (pin "4") (pinfunction "4_4") (pintype "passive"))
      (node (ref "REG1") (pin "2") (pinfunction "OUT_2") (pintype "passive"))
    )
    (net (code "207") (name "VDD") (class "Default")
      (node (ref "C2") (pin "1") (pinfunction "1_1") (pintype "passive"))
      (node (ref "C3") (pin "1") (pinfunction "1_1") (pintype "passive"))
      (node (ref "C4") (pin "1") (pinfunction "1_1") (pintype "passive"))
      (node (ref "C5") (pin "1") (pinfunction "1_1") (pintype "passive"))
      (node (ref "C6") (pin "1") (pinfunction "1_1") (pintype "passive"))
      (node (ref "D5") (pin "C") (pinfunction "C_C") (pintype "passive"))
      (node (ref "IC1") (pin "15") (pinfunction "A0_15") (pintype "input"))
      (node (ref "IC1") (pin "9") (pinfunction "VDD_9") (pintype "power_in"))
      (node (ref "IC2") (pin "16") (pinfunction "A1_16") (pintype "input"))
      (node (ref "IC2") (pin "9") (pinfunction "VDD_9") (pintype "power_in"))
      (node (ref "IC3") (pin "15") (pinfunction "A0_15") (pintype "input"))
      (node (ref "IC3") (pin "16") (pinfunction "A1_16") (pintype "input"))
      (node (ref "IC3") (pin "9") (pinfunction "VDD_9") (pintype "power_in"))
      (node (ref "IC4") (pin "17") (pinfunction "A2_17") (pintype "input"))
      (node (ref "IC4") (pin "9") (pinfunction "VDD_9") (pintype "power_in"))
      (node (ref "IC5") (pin "15") (pinfunction "A0_15") (pintype "input"))
      (node (ref "IC5") (pin "17") (pinfunction "A2_17") (pintype "input"))
      (node (ref "IC5") (pin "9") (pinfunction "VDD_9") (pintype "power_in"))
      (node (ref "J2") (pin "3") (pinfunction "S_3") (pintype "passive"))
      (node (ref "PWR") (pin "A") (pinfunction "A_A") (pintype "passive"))
    )
    (net (code "208") (name "VSS") (class "Default")
      (node (ref "18V_IN") (pin "2") (pinfunction "2_2") (pintype "passive"))
      (node (ref "C1") (pin "-") (pinfunction "-_-") (pintype "passive"))
      (node (ref "C2") (pin "2") (pinfunction "2_2") (pintype "passive"))
      (node (ref "C3") (pin "2") (pinfunction "2_2") (pintype "passive"))
      (node (ref "C4") (pin "2") (pinfunction "2_2") (pintype "passive"))
      (node (ref "C5") (pin "2") (pinfunction "2_2") (pintype "passive"))
      (node (ref "C6") (pin "2") (pinfunction "2_2") (pintype "passive"))
      (node (ref "IC1") (pin "10") (pinfunction "VSS_10") (pintype "power_in"))
      (node (ref "IC1") (pin "16") (pinfunction "A1_16") (pintype "input"))
      (node (ref "IC1") (pin "17") (pinfunction "A2_17") (pintype "input"))
      (node (ref "IC2") (pin "10") (pinfunction "VSS_10") (pintype "power_in"))
      (node (ref "IC2") (pin "15") (pinfunction "A0_15") (pintype "input"))
      (node (ref "IC2") (pin "17") (pinfunction "A2_17") (pintype "input"))
      (node (ref "IC3") (pin "10") (pinfunction "VSS_10") (pintype "power_in"))
      (node (ref "IC3") (pin "17") (pinfunction "A2_17") (pintype "input"))
      (node (ref "IC4") (pin "10") (pinfunction "VSS_10") (pintype "power_in"))
      (node (ref "IC4") (pin "15") (pinfunction "A0_15") (pintype "input"))
      (node (ref "IC4") (pin "16") (pinfunction "A1_16") (pintype "input"))
      (node (ref "IC5") (pin "10") (pinfunction "VSS_10") (pintype "power_in"))
      (node (ref "IC5") (pin "16") (pinfunction "A1_16") (pintype "input"))
      (node (ref "J2") (pin "1") (pinfunction "S_1") (pintype "passive"))
      (node (ref "R14") (pin "1") (pinfunction "1_1") (pintype "passive"))
      (node (ref "R2") (pin "1") (pinfunction "1_1") (pintype "passive"))
      (node (ref "R23") (pin "1") (pinfunction "1_1") (pintype "passive"))
      (node (ref "R3") (pin "1") (pinfunction "1_1") (pintype "passive"))
      (node (ref "R4") (pin "1") (pinfunction "1_1") (pintype "passive"))
      (node (ref "R5") (pin "1") (pinfunction "1_1") (pintype "passive"))
      (node (ref "RASPI") (pin "14") (pinfunction "14_14") (pintype "passive"))
      (node (ref "RASPI") (pin "20") (pinfunction "20_20") (pintype "passive"))
      (node (ref "RASPI") (pin "25") (pinfunction "25_25") (pintype "passive"))
      (node (ref "RASPI") (pin "30") (pinfunction "30_30") (pintype "passive"))
      (node (ref "RASPI") (pin "34") (pinfunction "34_34") (pintype "passive"))
      (node (ref "RASPI") (pin "39") (pinfunction "39_39") (pintype "passive"))
      (node (ref "RASPI") (pin "6") (pinfunction "6_6") (pintype "passive"))
      (node (ref "RASPI") (pin "9") (pinfunction "9_9") (pintype "passive"))
    )
    (net (code "209") (name "unconnected-(18V_IN-Pad3)") (class "Default")
      (node (ref "18V_IN") (pin "3") (pinfunction "3_3") (pintype "passive"))
    )
    (net (code "210") (name "unconnected-(IC1-INTA-Pad20)") (class "Default")
      (node (ref "IC1") (pin "20") (pinfunction "INTA_20") (pintype "output"))
    )
    (net (code "211") (name "unconnected-(IC1-INTB-Pad19)") (class "Default")
      (node (ref "IC1") (pin "19") (pinfunction "INTB_19") (pintype "output"))
    )
    (net (code "212") (name "unconnected-(IC2-INTA-Pad20)") (class "Default")
      (node (ref "IC2") (pin "20") (pinfunction "INTA_20") (pintype "output"))
    )
    (net (code "213") (name "unconnected-(IC2-INTB-Pad19)") (class "Default")
      (node (ref "IC2") (pin "19") (pinfunction "INTB_19") (pintype "output"))
    )
    (net (code "214") (name "unconnected-(IC3-INTA-Pad20)") (class "Default")
      (node (ref "IC3") (pin "20") (pinfunction "INTA_20") (pintype "output"))
    )
    (net (code "215") (name "unconnected-(IC3-INTB-Pad19)") (class "Default")
      (node (ref "IC3") (pin "19") (pinfunction "INTB_19") (pintype "output"))
    )
    (net (code "216") (name "unconnected-(IC4-INTA-Pad20)") (class "Default")
      (node (ref "IC4") (pin "20") (pinfunction "INTA_20") (pintype "output"))
    )
    (net (code "217") (name "unconnected-(IC4-INTB-Pad19)") (class "Default")
      (node (ref "IC4") (pin "19") (pinfunction "INTB_19") (pintype "output"))
    )
    (net (code "218") (name "unconnected-(IC5-INTA-Pad20)") (class "Default")
      (node (ref "IC5") (pin "20") (pinfunction "INTA_20") (pintype "output"))
    )
    (net (code "219") (name "unconnected-(IC5-INTB-Pad19)") (class "Default")
      (node (ref "IC5") (pin "19") (pinfunction "INTB_19") (pintype "output"))
    )
    (net (code "220") (name "unconnected-(UUTA-A1-Pad1)") (class "Default")
      (node (ref "UUT") (pin "1") (pinfunction "A1_1") (pintype "bidirectional"))
    )
    (net (code "221") (name "unconnected-(UUTA-B1-Pad4)") (class "Default")
      (node (ref "UUT") (pin "4") (pinfunction "B1_4") (pintype "bidirectional"))
    )
  )
)
